# M_2_SoM_breakout_board_V1_0.net
KiCad netlist of a schematic drawn in EAGLE
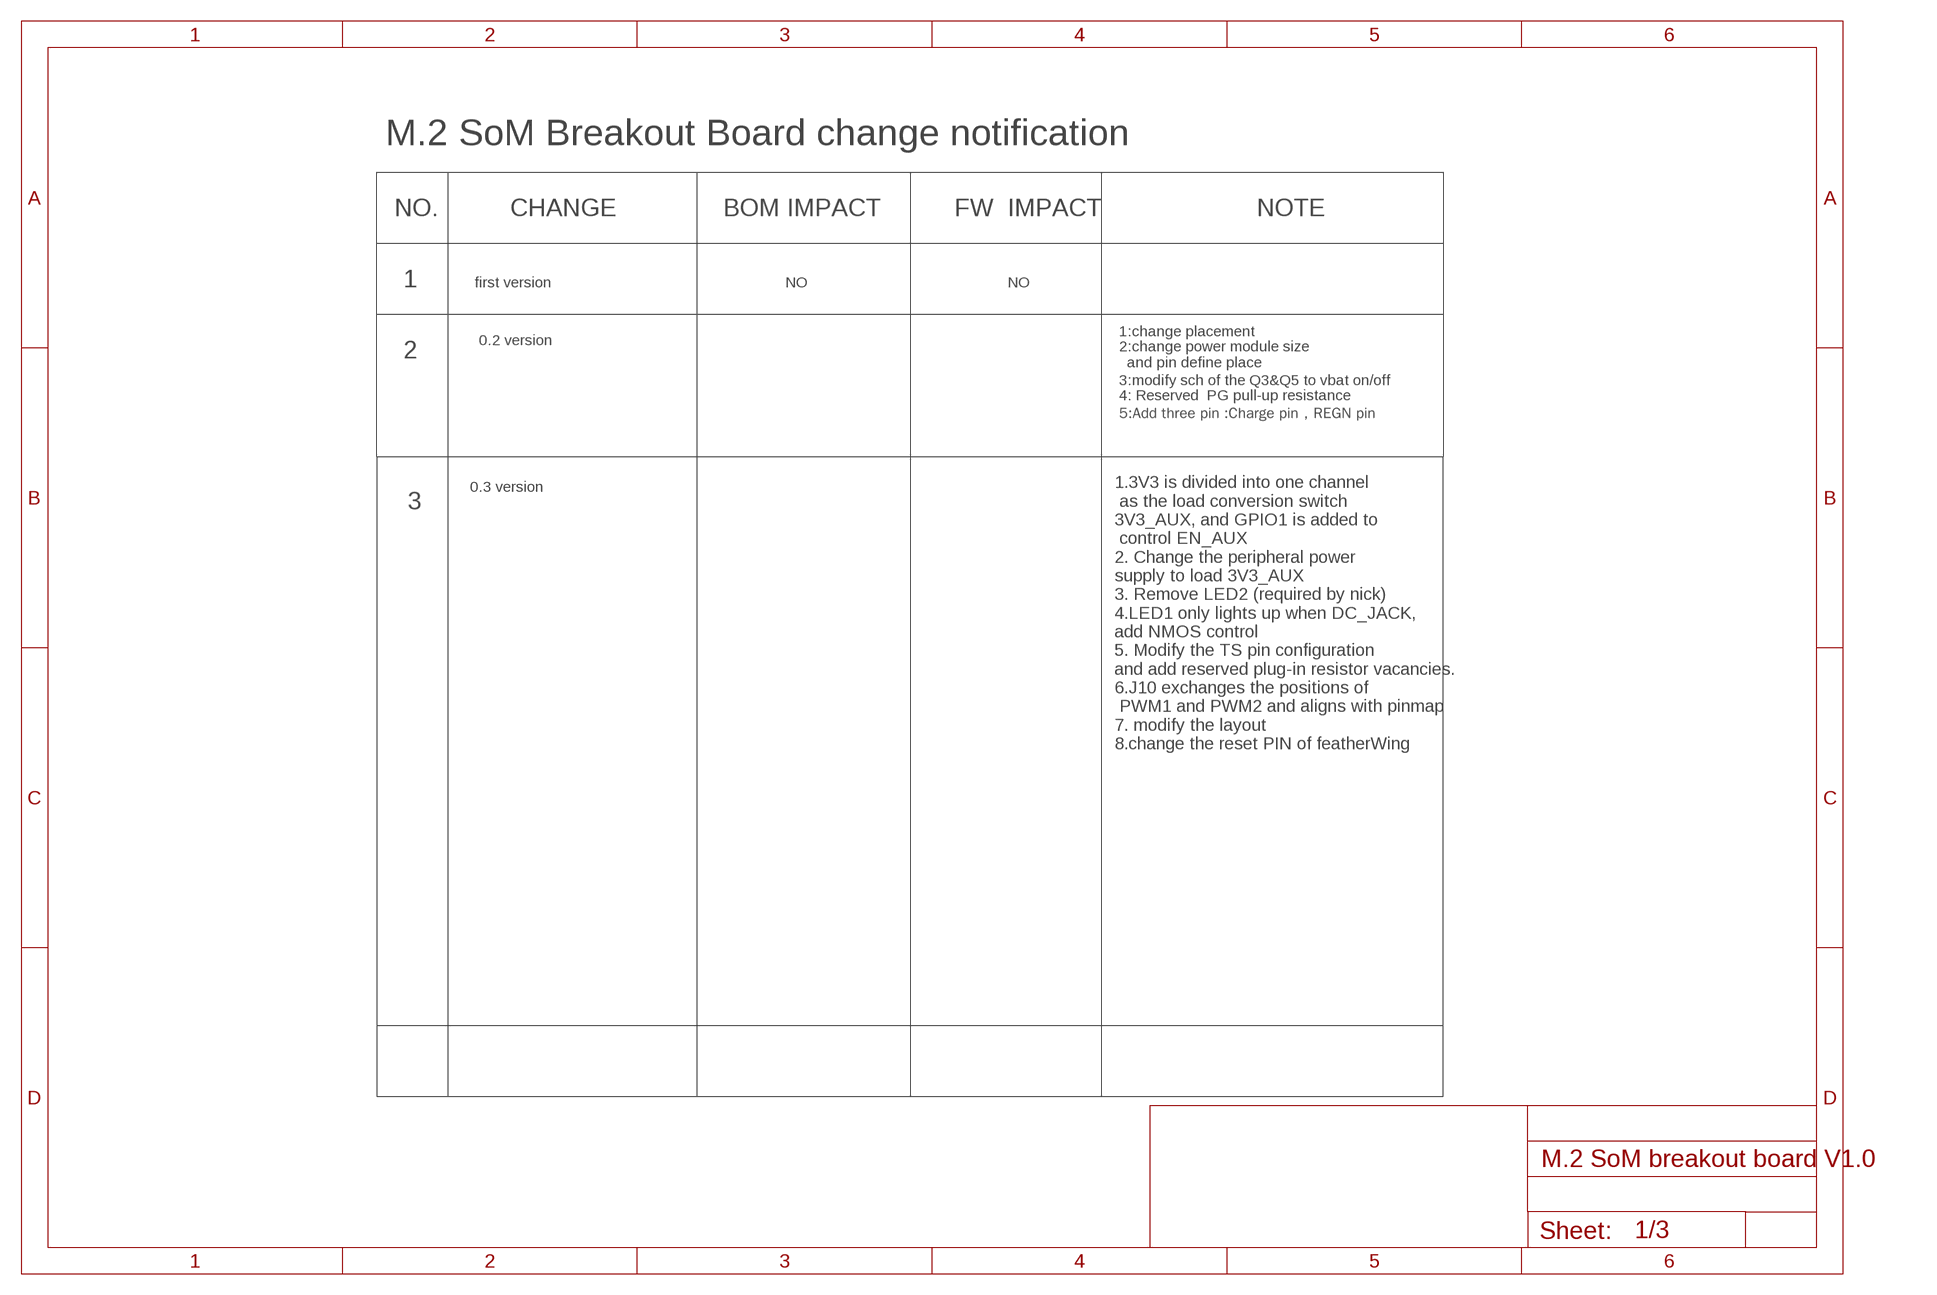
[diagram p0: schematic, sheet 1]
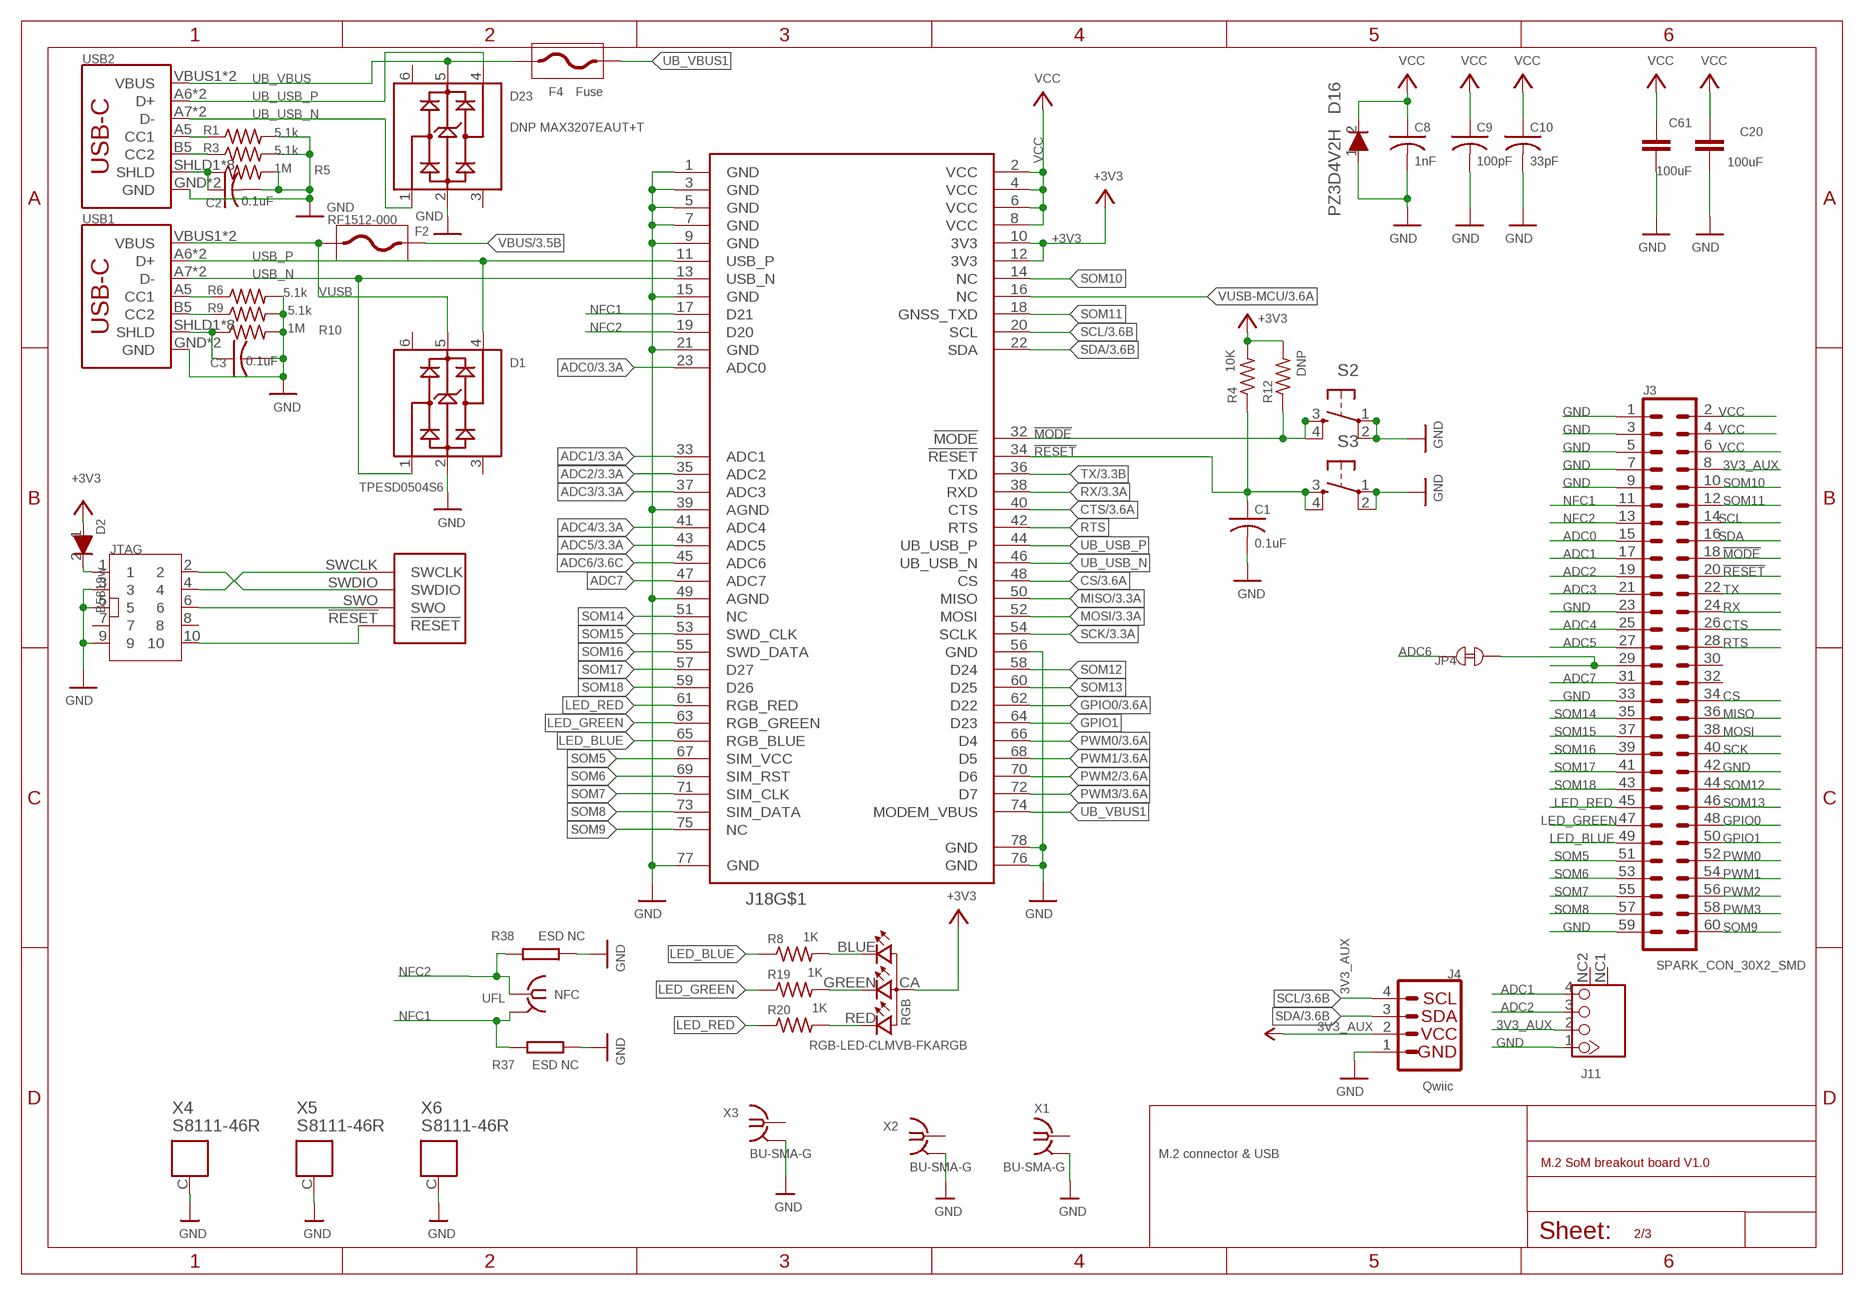
[diagram p1: schematic, sheet 2]
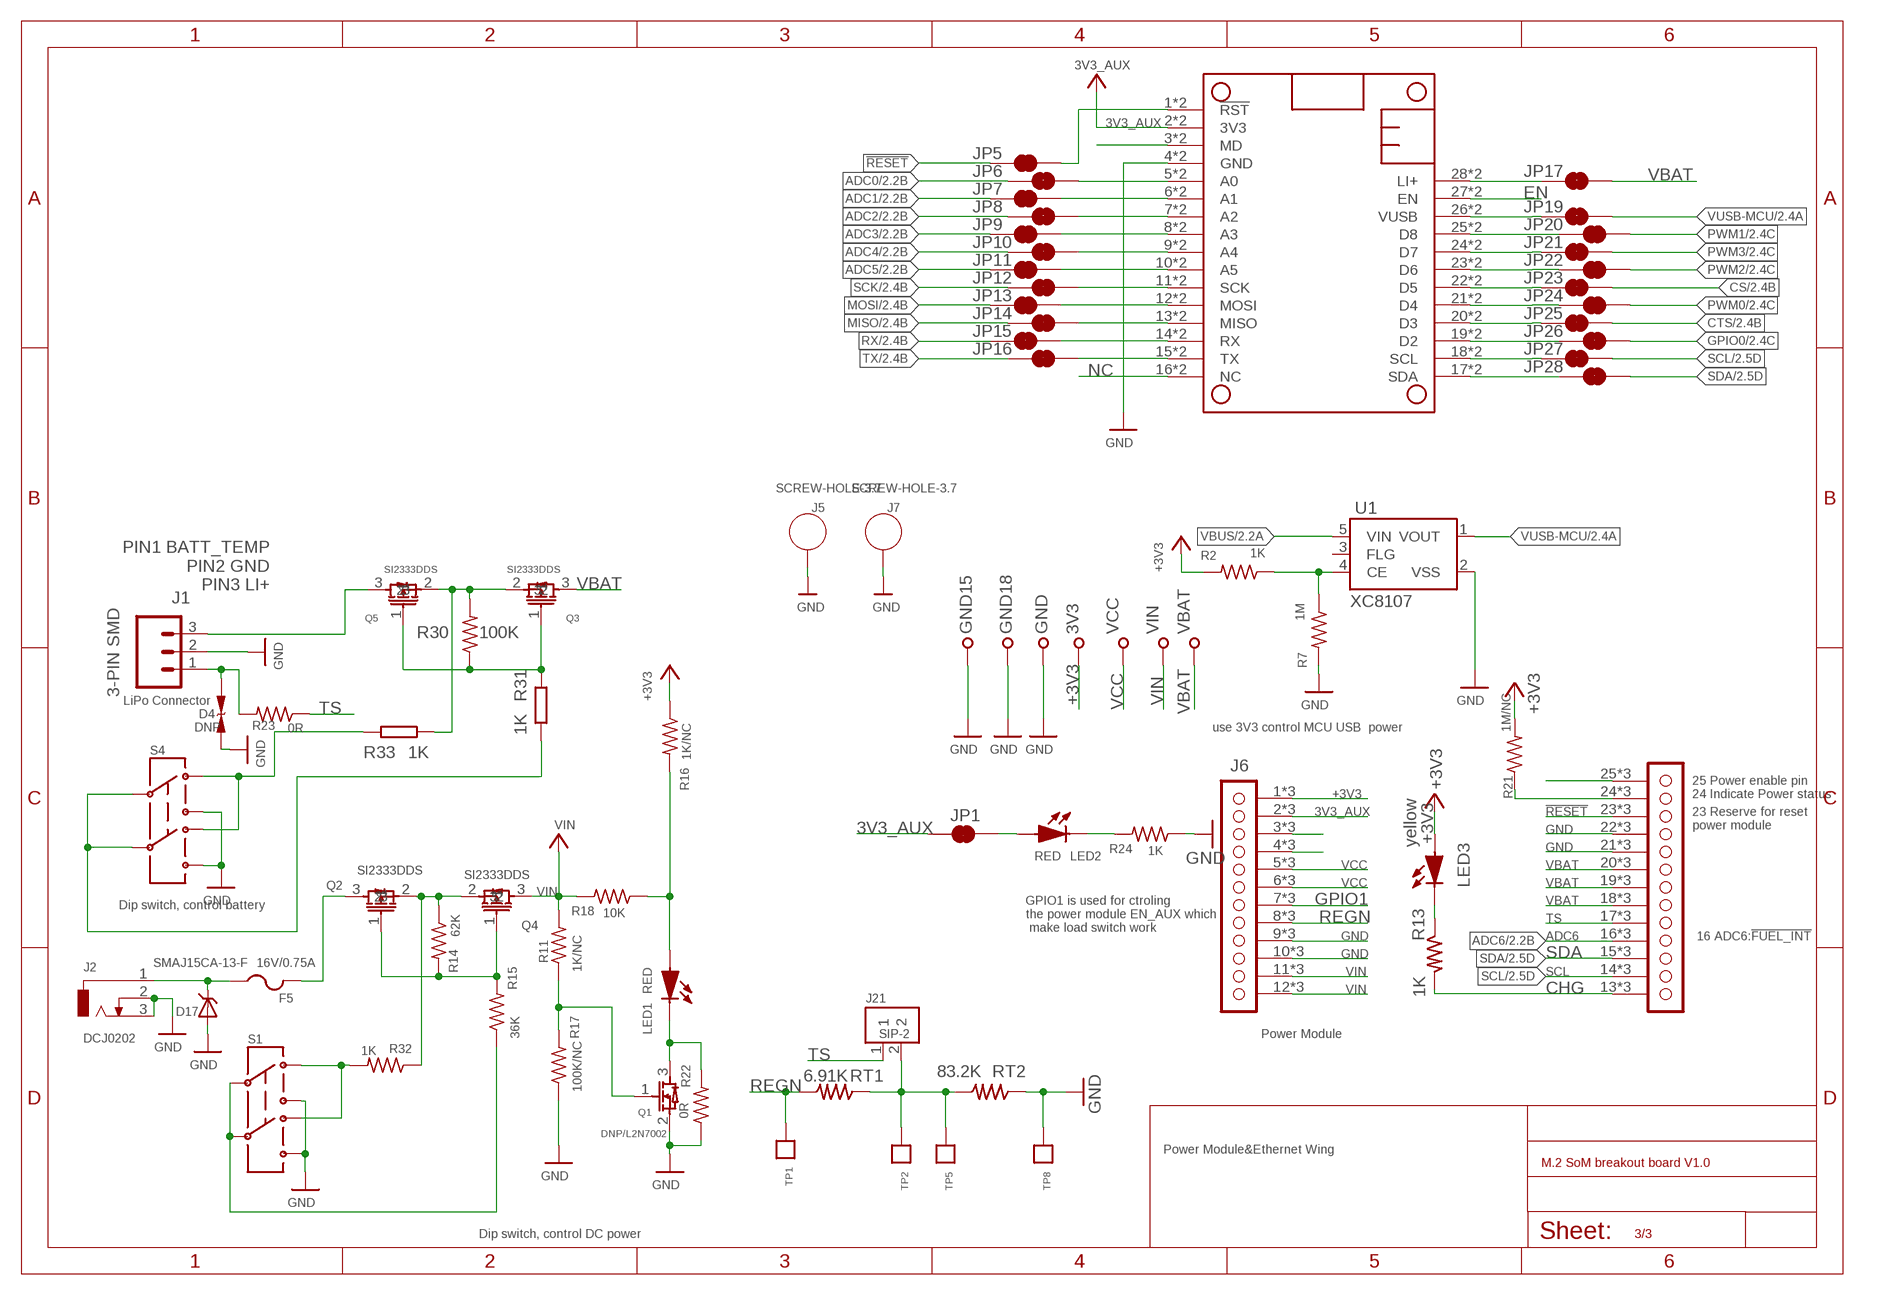
[diagram p2: schematic, sheet 3]

(export (version "E")
  (design (tool "Eeschema 10.0.6"))
  (components
    (comp (ref "C1")
      (value "0.1uF")
      (footprint "eagle-import:C0402_B")
      (libsource (lib "eagle-import") (part "C-US"))
    )
    (comp (ref "C2")
      (value "0.1uF")
      (footprint "eagle-import:C0402_B")
      (libsource (lib "eagle-import") (part "C-US"))
    )
    (comp (ref "C3")
      (value "0.1uF")
      (footprint "eagle-import:C0402_B")
      (libsource (lib "eagle-import") (part "C-US"))
    )
    (comp (ref "C8")
      (value "1nF")
      (footprint "eagle-import:C0402_B")
      (libsource (lib "eagle-import") (part "C-US"))
    )
    (comp (ref "C9")
      (value "100pF")
      (footprint "eagle-import:C0402_B")
      (libsource (lib "eagle-import") (part "C-US"))
    )
    (comp (ref "C10")
      (value "33pF")
      (footprint "eagle-import:C0402_B")
      (libsource (lib "eagle-import") (part "C-US"))
    )
    (comp (ref "C20")
      (value "100uF")
      (footprint "eagle-import:C1206K")
      (libsource (lib "eagle-import") (part "C-EUC1206K"))
    )
    (comp (ref "C61")
      (value "100uF")
      (footprint "eagle-import:C1206K")
      (libsource (lib "eagle-import") (part "C-EUC1206K"))
    )
    (comp (ref "D1")
      (value "TPESD0504S6")
      (footprint "eagle-import:SOT23-6")
      (fields (field (name "MFG") "MAXIM") (field (name "MPN") "MAX3207EAUT+T"))
      (libsource (lib "eagle-import") (part "MAX3207EAUT+T"))
    )
    (comp (ref "D2")
      (value "B5819w")
      (footprint "eagle-import:SOD-123")
      (libsource (lib "eagle-import") (part "DIODESOD123"))
    )
    (comp (ref "D16")
      (value "PZ3D4V2H")
      (footprint "eagle-import:SOD-323")
      (libsource (lib "eagle-import") (part "DIODESOD323"))
    )
    (comp (ref "D23")
      (value "DNP MAX3207EAUT+T")
      (footprint "eagle-import:SOT23-6")
      (fields (field (name "MFG") "MAXIM") (field (name "MPN") "MAX3207EAUT+T"))
      (libsource (lib "eagle-import") (part "MAX3207EAUT+T"))
    )
    (comp (ref "F2")
      (value "RF1512-000")
      (footprint "eagle-import:F0805")
      (libsource (lib "eagle-import") (part "FUSE"))
    )
    (comp (ref "F4")
      (value "Fuse")
      (footprint "eagle-import:F0805")
      (libsource (lib "eagle-import") (part "FUSE"))
    )
    (comp (ref "J3")
      (value "SPARK_CON_30X2_SMD")
      (footprint "eagle-import:SPARK_CON_30X2_SMD")
      (libsource (lib "eagle-import") (part "SPARK_CON_30X2_SMD"))
    )
    (comp (ref "J4")
      (value "QWIIC_CONNECTORJS-1MM")
      (footprint "eagle-import:1X04_1MM_RA")
      (libsource (lib "eagle-import") (part "QWIIC_CONNECTORJS-1MM"))
    )
    (comp (ref "J11")
      (value "WAFER-HY2.0-4PWB")
      (footprint "eagle-import:M.2-SOM-BREAKOUT-BOARD-V0.2-0228_WAFER-HY2.0-4PWB")
      (libsource (lib "eagle-import") (part "M.2-SOM-BREAKOUT-BOARD-V0.2-0228_WAFER-HY2.0-4PWB"))
    )
    (comp (ref "J18")
      (value "PARTICLE-STUDIOS_M_SERIES_M.2KEY")
      (footprint "eagle-import:PARTICLE-STUDIOS_PARTICLE_M.2EKEY_3.65MM_DRILL")
      (libsource (lib "eagle-import") (part "PARTICLE-STUDIOS_M_SERIES_M.2KEY"))
    )
    (comp (ref "JP4")
      (value "TP_SHORT")
      (footprint "eagle-import:TP_SHORT")
      (libsource (lib "eagle-import") (part "TP_SHORT"))
    )
    (comp (ref "JTAG")
      (value "CONN5X2")
      (footprint "eagle-import:CONN5X2_1.27")
      (fields (field (name "MFG") "KAWEEI") (field (name "MPN") "P6014A-M2GC-030-10"))
      (libsource (lib "eagle-import") (part "CONN5X2"))
    )
    (comp (ref "NFC")
      (value "UFL")
      (footprint "eagle-import:IPEX-20279-001E")
      (libsource (lib "eagle-import") (part "IPEX-20279-001E"))
    )
    (comp (ref "R1")
      (value "5.1k")
      (footprint "eagle-import:R0402_B")
      (libsource (lib "eagle-import") (part "R-US_"))
    )
    (comp (ref "R3")
      (value "5.1k")
      (footprint "eagle-import:R0402_B")
      (libsource (lib "eagle-import") (part "R-US_"))
    )
    (comp (ref "R4")
      (value "10K")
      (footprint "eagle-import:R0402_B")
      (libsource (lib "eagle-import") (part "R-US_"))
    )
    (comp (ref "R5")
      (value "1M")
      (footprint "eagle-import:R0402_B")
      (libsource (lib "eagle-import") (part "R-US_"))
    )
    (comp (ref "R6")
      (value "5.1k")
      (footprint "eagle-import:R0402_B")
      (libsource (lib "eagle-import") (part "R-US_"))
    )
    (comp (ref "R8")
      (value "1K")
      (footprint "eagle-import:R0402_B")
      (libsource (lib "eagle-import") (part "R-US_"))
    )
    (comp (ref "R9")
      (value "5.1k")
      (footprint "eagle-import:R0402_B")
      (libsource (lib "eagle-import") (part "R-US_"))
    )
    (comp (ref "R10")
      (value "1M")
      (footprint "eagle-import:R0402_B")
      (libsource (lib "eagle-import") (part "R-US_"))
    )
    (comp (ref "R12")
      (value "DNP")
      (footprint "eagle-import:R0402_B")
      (libsource (lib "eagle-import") (part "R-US_"))
    )
    (comp (ref "R19")
      (value "1K")
      (footprint "eagle-import:R0402_B")
      (libsource (lib "eagle-import") (part "R-US_"))
    )
    (comp (ref "R20")
      (value "1K")
      (footprint "eagle-import:R0402_B")
      (libsource (lib "eagle-import") (part "R-US_"))
    )
    (comp (ref "R37")
      (value "ESD NC")
      (footprint "eagle-import:R-0402S")
      (libsource (lib "eagle-import") (part "RES0402S"))
    )
    (comp (ref "R38")
      (value "ESD NC")
      (footprint "eagle-import:R-0402S")
      (libsource (lib "eagle-import") (part "RES0402S"))
    )
    (comp (ref "RGB")
      (value "RGB-LED-CLMVB-FKARGB")
      (footprint "eagle-import:PLCC4-2MM-RGB")
      (libsource (lib "eagle-import") (part "RGB-LED-CLMVB-FKARGB"))
    )
    (comp (ref "S2")
      (value "TAC_SWITCH")
      (footprint "eagle-import:TACTILE_SWITCH_4.2_3.2")
      (libsource (lib "eagle-import") (part "TAC_SWITCH"))
    )
    (comp (ref "S3")
      (value "TAC_SWITCH")
      (footprint "eagle-import:TACTILE_SWITCH_4.2_3.2")
      (libsource (lib "eagle-import") (part "TAC_SWITCH"))
    )
    (comp (ref "USB1")
      (value "USB_C16PIN")
      (footprint "eagle-import:USB-C-16P")
      (libsource (lib "eagle-import") (part "USB_C16PIN"))
    )
    (comp (ref "USB2")
      (value "USB_C16PIN")
      (footprint "eagle-import:USB-C-16P")
      (libsource (lib "eagle-import") (part "USB_C16PIN"))
    )
    (comp (ref "X1")
      (value "BU-SMA-G")
      (footprint "eagle-import:BU-SMA-G")
      (libsource (lib "eagle-import") (part "BU-SMA-G"))
    )
    (comp (ref "X2")
      (value "BU-SMA-G")
      (footprint "eagle-import:BU-SMA-G")
      (libsource (lib "eagle-import") (part "BU-SMA-G"))
    )
    (comp (ref "X3")
      (value "BU-SMA-G")
      (footprint "eagle-import:BU-SMA-G")
      (libsource (lib "eagle-import") (part "BU-SMA-G"))
    )
    (comp (ref "X4")
      (value "S8111-46R")
      (footprint "eagle-import:S8111-46R")
      (libsource (lib "eagle-import") (part "S8111-46R"))
    )
    (comp (ref "X5")
      (value "S8111-46R")
      (footprint "eagle-import:S8111-46R")
      (libsource (lib "eagle-import") (part "S8111-46R"))
    )
    (comp (ref "X6")
      (value "S8111-46R")
      (footprint "eagle-import:S8111-46R")
      (libsource (lib "eagle-import") (part "S8111-46R"))
    )
    (comp (ref "3V3")
      (value "TP-S2751-46R")
      (footprint "eagle-import:S2751-46R")
      (libsource (lib "eagle-import") (part "TP-S2751-46R"))
    )
    (comp (ref "D4")
      (value "DNP")
      (footprint "eagle-import:C0402")
      (libsource (lib "eagle-import") (part "ESD"))
    )
    (comp (ref "D17")
      (value "SMAJ15CA-13-F")
      (footprint "eagle-import:SMADIODE")
      (libsource (lib "eagle-import") (part "DIODE-ZENER"))
    )
    (comp (ref "F5")
      (value "16V/0.75A")
      (footprint "eagle-import:1812")
      (libsource (lib "eagle-import") (part "PTCFUSE-1812"))
    )
    (comp (ref "GND")
      (value "TP-S2751-46R")
      (footprint "eagle-import:S2751-46R")
      (libsource (lib "eagle-import") (part "TP-S2751-46R"))
    )
    (comp (ref "GND15")
      (value "TP-S2751-46R")
      (footprint "eagle-import:S2751-46R")
      (libsource (lib "eagle-import") (part "TP-S2751-46R"))
    )
    (comp (ref "GND18")
      (value "TP-S2751-46R")
      (footprint "eagle-import:S2751-46R")
      (libsource (lib "eagle-import") (part "TP-S2751-46R"))
    )
    (comp (ref "J1")
      (value "3-PIN SMD")
      (footprint "eagle-import:JST-3-SMD")
      (libsource (lib "eagle-import") (part "CONN_03JST-SMD"))
    )
    (comp (ref "J2")
      (value "DCJ0202")
      (footprint "eagle-import:DCJ0202")
      (libsource (lib "eagle-import") (part "DCJ0202"))
    )
    (comp (ref "J5")
      (value "SCREW-HOLE-3.7")
      (footprint "eagle-import:SCREW-HOLE-3.7")
      (libsource (lib "eagle-import") (part "SCREW-HOLE-3.7"))
    )
    (comp (ref "J6")
      (value "M.2-SOM-BREAKOUT-BOARD-V0.3_M.2-SOM-BREAKOUT-BOARD-V0.2-0228_PARTICLE-SZ_PARTICLE-POWER-MODULE")
      (footprint "eagle-import:M.2-SOM-BREAKOUT-BOARD-V0.3_M.2-SOM-BREAKOUT-BOARD-V0.2-0228_PARTICLE-SZ_PARTICLE-POWER-MODULE")
      (libsource (lib "eagle-import") (part "M.2-SOM-BREAKOUT-BOARD-V0.3_M.2-SOM-BREAKOUT-BOARD-V0.2-0228_PARTICLE-SZ_PARTICLE-POWER-MODULE"))
    )
    (comp (ref "J7")
      (value "SCREW-HOLE-3.7")
      (footprint "eagle-import:SCREW-HOLE-3.7")
      (libsource (lib "eagle-import") (part "SCREW-HOLE-3.7"))
    )
    (comp (ref "J21")
      (value "SIP-2")
      (footprint "eagle-import:SIP-2")
      (libsource (lib "eagle-import") (part "SIP-2"))
    )
    (comp (ref "JP1")
      (value "JUMPER-SMT_2_NC_TRACE_NO-SILK")
      (footprint "eagle-import:SMT-JUMPER_2_NC_TRACE_NO-SILK")
      (libsource (lib "eagle-import") (part "JUMPER-SMT_2_NC_TRACE_NO-SILK"))
    )
    (comp (ref "JP5")
      (value "JUMPER-SMT_2_NC_TRACE_NO-SILK")
      (footprint "eagle-import:SMT-JUMPER_2_NC_TRACE_NO-SILK")
      (libsource (lib "eagle-import") (part "JUMPER-SMT_2_NC_TRACE_NO-SILK"))
    )
    (comp (ref "JP6")
      (value "JUMPER-SMT_2_NC_TRACE_NO-SILK")
      (footprint "eagle-import:SMT-JUMPER_2_NC_TRACE_NO-SILK")
      (libsource (lib "eagle-import") (part "JUMPER-SMT_2_NC_TRACE_NO-SILK"))
    )
    (comp (ref "JP7")
      (value "JUMPER-SMT_2_NC_TRACE_NO-SILK")
      (footprint "eagle-import:SMT-JUMPER_2_NC_TRACE_NO-SILK")
      (libsource (lib "eagle-import") (part "JUMPER-SMT_2_NC_TRACE_NO-SILK"))
    )
    (comp (ref "JP8")
      (value "JUMPER-SMT_2_NC_TRACE_NO-SILK")
      (footprint "eagle-import:SMT-JUMPER_2_NC_TRACE_NO-SILK")
      (libsource (lib "eagle-import") (part "JUMPER-SMT_2_NC_TRACE_NO-SILK"))
    )
    (comp (ref "JP9")
      (value "JUMPER-SMT_2_NC_TRACE_NO-SILK")
      (footprint "eagle-import:SMT-JUMPER_2_NC_TRACE_NO-SILK")
      (libsource (lib "eagle-import") (part "JUMPER-SMT_2_NC_TRACE_NO-SILK"))
    )
    (comp (ref "JP10")
      (value "JUMPER-SMT_2_NC_TRACE_NO-SILK")
      (footprint "eagle-import:SMT-JUMPER_2_NC_TRACE_NO-SILK")
      (libsource (lib "eagle-import") (part "JUMPER-SMT_2_NC_TRACE_NO-SILK"))
    )
    (comp (ref "JP11")
      (value "JUMPER-SMT_2_NC_TRACE_NO-SILK")
      (footprint "eagle-import:SMT-JUMPER_2_NC_TRACE_NO-SILK")
      (libsource (lib "eagle-import") (part "JUMPER-SMT_2_NC_TRACE_NO-SILK"))
    )
    (comp (ref "JP12")
      (value "JUMPER-SMT_2_NC_TRACE_NO-SILK")
      (footprint "eagle-import:SMT-JUMPER_2_NC_TRACE_NO-SILK")
      (libsource (lib "eagle-import") (part "JUMPER-SMT_2_NC_TRACE_NO-SILK"))
    )
    (comp (ref "JP13")
      (value "JUMPER-SMT_2_NC_TRACE_NO-SILK")
      (footprint "eagle-import:SMT-JUMPER_2_NC_TRACE_NO-SILK")
      (libsource (lib "eagle-import") (part "JUMPER-SMT_2_NC_TRACE_NO-SILK"))
    )
    (comp (ref "JP14")
      (value "JUMPER-SMT_2_NC_TRACE_NO-SILK")
      (footprint "eagle-import:SMT-JUMPER_2_NC_TRACE_NO-SILK")
      (libsource (lib "eagle-import") (part "JUMPER-SMT_2_NC_TRACE_NO-SILK"))
    )
    (comp (ref "JP15")
      (value "JUMPER-SMT_2_NC_TRACE_NO-SILK")
      (footprint "eagle-import:SMT-JUMPER_2_NC_TRACE_NO-SILK")
      (libsource (lib "eagle-import") (part "JUMPER-SMT_2_NC_TRACE_NO-SILK"))
    )
    (comp (ref "JP16")
      (value "JUMPER-SMT_2_NC_TRACE_NO-SILK")
      (footprint "eagle-import:SMT-JUMPER_2_NC_TRACE_NO-SILK")
      (libsource (lib "eagle-import") (part "JUMPER-SMT_2_NC_TRACE_NO-SILK"))
    )
    (comp (ref "JP17")
      (value "JUMPER-SMT_2_NC_TRACE_NO-SILK")
      (footprint "eagle-import:SMT-JUMPER_2_NC_TRACE_NO-SILK")
      (libsource (lib "eagle-import") (part "JUMPER-SMT_2_NC_TRACE_NO-SILK"))
    )
    (comp (ref "JP19")
      (value "JUMPER-SMT_2_NC_TRACE_NO-SILK")
      (footprint "eagle-import:SMT-JUMPER_2_NC_TRACE_NO-SILK")
      (libsource (lib "eagle-import") (part "JUMPER-SMT_2_NC_TRACE_NO-SILK"))
    )
    (comp (ref "JP20")
      (value "JUMPER-SMT_2_NC_TRACE_NO-SILK")
      (footprint "eagle-import:SMT-JUMPER_2_NC_TRACE_NO-SILK")
      (libsource (lib "eagle-import") (part "JUMPER-SMT_2_NC_TRACE_NO-SILK"))
    )
    (comp (ref "JP21")
      (value "JUMPER-SMT_2_NC_TRACE_NO-SILK")
      (footprint "eagle-import:SMT-JUMPER_2_NC_TRACE_NO-SILK")
      (libsource (lib "eagle-import") (part "JUMPER-SMT_2_NC_TRACE_NO-SILK"))
    )
    (comp (ref "JP22")
      (value "JUMPER-SMT_2_NC_TRACE_NO-SILK")
      (footprint "eagle-import:SMT-JUMPER_2_NC_TRACE_NO-SILK")
      (libsource (lib "eagle-import") (part "JUMPER-SMT_2_NC_TRACE_NO-SILK"))
    )
    (comp (ref "JP23")
      (value "JUMPER-SMT_2_NC_TRACE_NO-SILK")
      (footprint "eagle-import:SMT-JUMPER_2_NC_TRACE_NO-SILK")
      (libsource (lib "eagle-import") (part "JUMPER-SMT_2_NC_TRACE_NO-SILK"))
    )
    (comp (ref "JP24")
      (value "JUMPER-SMT_2_NC_TRACE_NO-SILK")
      (footprint "eagle-import:SMT-JUMPER_2_NC_TRACE_NO-SILK")
      (libsource (lib "eagle-import") (part "JUMPER-SMT_2_NC_TRACE_NO-SILK"))
    )
    (comp (ref "JP25")
      (value "JUMPER-SMT_2_NC_TRACE_NO-SILK")
      (footprint "eagle-import:SMT-JUMPER_2_NC_TRACE_NO-SILK")
      (libsource (lib "eagle-import") (part "JUMPER-SMT_2_NC_TRACE_NO-SILK"))
    )
    (comp (ref "JP26")
      (value "JUMPER-SMT_2_NC_TRACE_NO-SILK")
      (footprint "eagle-import:SMT-JUMPER_2_NC_TRACE_NO-SILK")
      (libsource (lib "eagle-import") (part "JUMPER-SMT_2_NC_TRACE_NO-SILK"))
    )
    (comp (ref "JP27")
      (value "JUMPER-SMT_2_NC_TRACE_NO-SILK")
      (footprint "eagle-import:SMT-JUMPER_2_NC_TRACE_NO-SILK")
      (libsource (lib "eagle-import") (part "JUMPER-SMT_2_NC_TRACE_NO-SILK"))
    )
    (comp (ref "JP28")
      (value "JUMPER-SMT_2_NC_TRACE_NO-SILK")
      (footprint "eagle-import:SMT-JUMPER_2_NC_TRACE_NO-SILK")
      (libsource (lib "eagle-import") (part "JUMPER-SMT_2_NC_TRACE_NO-SILK"))
    )
    (comp (ref "LED1")
      (value "RED")
      (footprint "eagle-import:LED0603")
      (libsource (lib "eagle-import") (part "LED"))
    )
    (comp (ref "LED2")
      (value "RED")
      (footprint "eagle-import:LED0603")
      (libsource (lib "eagle-import") (part "LED"))
    )
    (comp (ref "LED3")
      (value "yellow")
      (footprint "eagle-import:LED0603")
      (libsource (lib "eagle-import") (part "LED"))
    )
    (comp (ref "MS1")
      (value "PARTICLE_MESH_SMTDUAL")
      (footprint "eagle-import:FEATHERWING_SMT2")
      (libsource (lib "eagle-import") (part "PARTICLE_MESH_SMTDUAL"))
    )
    (comp (ref "Q1")
      (value "DNP/L2N7002")
      (footprint "eagle-import:SOT323")
      (libsource (lib "eagle-import") (part "NMOSSOT323"))
    )
    (comp (ref "Q2")
      (value "SI2333DDS")
      (footprint "eagle-import:SOT-23")
      (libsource (lib "eagle-import") (part "PMOS"))
    )
    (comp (ref "Q3")
      (value "SI2333DDS")
      (footprint "eagle-import:SOT-23")
      (libsource (lib "eagle-import") (part "PMOS"))
    )
    (comp (ref "Q4")
      (value "SI2333DDS")
      (footprint "eagle-import:SOT-23")
      (libsource (lib "eagle-import") (part "PMOS"))
    )
    (comp (ref "Q5")
      (value "SI2333DDS")
      (footprint "eagle-import:SOT-23")
      (libsource (lib "eagle-import") (part "PMOS"))
    )
    (comp (ref "R2")
      (value "1K")
      (footprint "eagle-import:R0402_B")
      (libsource (lib "eagle-import") (part "R-US_"))
    )
    (comp (ref "R7")
      (value "1M")
      (footprint "eagle-import:R0402_B")
      (libsource (lib "eagle-import") (part "R-US_"))
    )
    (comp (ref "R11")
      (value "1K/NC")
      (footprint "eagle-import:R0402_B")
      (libsource (lib "eagle-import") (part "R-US_"))
    )
    (comp (ref "R13")
      (value "1K")
      (footprint "eagle-import:R-0402S")
      (libsource (lib "eagle-import") (part "particle SZ_RES0402S"))
    )
    (comp (ref "R14")
      (value "62K")
      (footprint "eagle-import:R0402_B")
      (libsource (lib "eagle-import") (part "R-US_"))
    )
    (comp (ref "R15")
      (value "36K")
      (footprint "eagle-import:R0402_B")
      (libsource (lib "eagle-import") (part "R-US_"))
    )
    (comp (ref "R16")
      (value "1K/NC")
      (footprint "eagle-import:R0402_B")
      (libsource (lib "eagle-import") (part "R-US_"))
    )
    (comp (ref "R17")
      (value "100K/NC")
      (footprint "eagle-import:R0402_B")
      (libsource (lib "eagle-import") (part "R-US_"))
    )
    (comp (ref "R18")
      (value "10K")
      (footprint "eagle-import:R0402_B")
      (libsource (lib "eagle-import") (part "R-US_"))
    )
    (comp (ref "R21")
      (value "1M/NC")
      (footprint "eagle-import:R0402_B")
      (libsource (lib "eagle-import") (part "R-US_"))
    )
    (comp (ref "R22")
      (value "0R")
      (footprint "eagle-import:R0402_B")
      (libsource (lib "eagle-import") (part "R-US_"))
    )
    (comp (ref "R23")
      (value "0R")
      (footprint "eagle-import:R0402_B")
      (libsource (lib "eagle-import") (part "R-US_"))
    )
    (comp (ref "R24")
      (value "1K")
      (footprint "eagle-import:R0402_B")
      (libsource (lib "eagle-import") (part "R-US_"))
    )
    (comp (ref "R30")
      (value "100K")
      (footprint "eagle-import:R0603_P")
      (libsource (lib "eagle-import") (part "RES_0603100K_"))
    )
    (comp (ref "R31")
      (value "1K")
      (footprint "eagle-import:R-0402S")
      (libsource (lib "eagle-import") (part "RES0402S"))
    )
    (comp (ref "R32")
      (value "1K")
      (footprint "eagle-import:R0402_B")
      (libsource (lib "eagle-import") (part "R-US_"))
    )
    (comp (ref "R33")
      (value "1K")
      (footprint "eagle-import:R-0402S")
      (libsource (lib "eagle-import") (part "RES0402S"))
    )
    (comp (ref "RT1")
      (value "6.91K")
      (footprint "eagle-import:R-0603A")
      (libsource (lib "eagle-import") (part "RESR0603A"))
    )
    (comp (ref "RT2")
      (value "83.2K")
      (footprint "eagle-import:R-0603A")
      (libsource (lib "eagle-import") (part "RESR0603A"))
    )
    (comp (ref "S1")
      (value "SWITCH-DPDT")
      (footprint "eagle-import:SWITCH-2.5X3.2-6")
      (libsource (lib "eagle-import") (part "SWITCH-DPDT"))
    )
    (comp (ref "S4")
      (value "SWITCH-DPDT")
      (footprint "eagle-import:SWITCH-2.5X3.2-6")
      (libsource (lib "eagle-import") (part "SWITCH-DPDT"))
    )
    (comp (ref "TP1")
      (value "TPTPEB")
      (footprint "eagle-import:TPEB")
      (libsource (lib "eagle-import") (part "TPTPEB"))
    )
    (comp (ref "TP2")
      (value "TPTPEB")
      (footprint "eagle-import:TPEB")
      (libsource (lib "eagle-import") (part "TPTPEB"))
    )
    (comp (ref "TP5")
      (value "TPTPEB")
      (footprint "eagle-import:TPEB")
      (libsource (lib "eagle-import") (part "TPTPEB"))
    )
    (comp (ref "TP8")
      (value "TPTPEB")
      (footprint "eagle-import:TPEB")
      (libsource (lib "eagle-import") (part "TPTPEB"))
    )
    (comp (ref "U1")
      (value "XC8107")
      (footprint "eagle-import:SOT25")
      (libsource (lib "eagle-import") (part "XC8107SOT25"))
    )
    (comp (ref "VBAT")
      (value "TP-S2751-46R")
      (footprint "eagle-import:S2751-46R")
      (libsource (lib "eagle-import") (part "TP-S2751-46R"))
    )
    (comp (ref "VCC")
      (value "TP-S2751-46R")
      (footprint "eagle-import:S2751-46R")
      (libsource (lib "eagle-import") (part "TP-S2751-46R"))
    )
    (comp (ref "VIN")
      (value "TP-S2751-46R")
      (footprint "eagle-import:S2751-46R")
      (libsource (lib "eagle-import") (part "TP-S2751-46R"))
    )
  )
  (nets
    (net (code "1") (name "+3V3") (class "Default")
      (node (ref "3V3") (pin "1") (pinfunction "TP_1") (pintype "bidirectional"))
      (node (ref "D2") (pin "1") (pinfunction "P$1_1") (pintype "bidirectional"))
      (node (ref "J18") (pin "10") (pinfunction "3V3_10") (pintype "power_in"))
      (node (ref "J18") (pin "12") (pinfunction "3V3_12") (pintype "power_in"))
      (node (ref "J6") (pin "1") (pinfunction "3V3_1") (pintype "passive"))
      (node (ref "J6") (pin "@1") (pinfunction "3V3_@1") (pintype "passive"))
      (node (ref "J6") (pin "P$1") (pinfunction "3V3_P$1") (pintype "passive"))
      (node (ref "LED3") (pin "1") (pinfunction "A_1") (pintype "bidirectional"))
      (node (ref "R12") (pin "2") (pinfunction "2_2") (pintype "passive"))
      (node (ref "R16") (pin "1") (pinfunction "1_1") (pintype "passive"))
      (node (ref "R2") (pin "2") (pinfunction "2_2") (pintype "passive"))
      (node (ref "R21") (pin "2") (pinfunction "2_2") (pintype "passive"))
      (node (ref "R4") (pin "2") (pinfunction "2_2") (pintype "passive"))
      (node (ref "RGB") (pin "CA") (pinfunction "1_CA") (pintype "passive"))
    )
    (net (code "2") (name "3V3_AUX") (class "Default")
      (node (ref "J11") (pin "2") (pinfunction "2_2") (pintype "bidirectional"))
      (node (ref "J3") (pin "8") (pinfunction "8_8") (pintype "passive"))
      (node (ref "J4") (pin "2") (pinfunction "2_2") (pintype "power_in"))
      (node (ref "J6") (pin "2") (pinfunction "3V3_2") (pintype "passive"))
      (node (ref "J6") (pin "@2") (pinfunction "3V3_@2") (pintype "passive"))
      (node (ref "J6") (pin "P$2") (pinfunction "3V3_P$2") (pintype "passive"))
      (node (ref "JP1") (pin "1") (pinfunction "1_1") (pintype "passive"))
      (node (ref "MS1") (pin "2") (pinfunction "3V3_2") (pintype "power_in"))
      (node (ref "MS1") (pin "2'") (pinfunction "3V3_2'") (pintype "power_in"))
    )
    (net (code "3") (name "ADC0") (class "Default")
      (node (ref "J18") (pin "23") (pinfunction "ADC0_23") (pintype "bidirectional"))
      (node (ref "J3") (pin "15") (pinfunction "15_15") (pintype "passive"))
      (node (ref "JP6") (pin "1") (pinfunction "1_1") (pintype "passive"))
    )
    (net (code "4") (name "ADC1") (class "Default")
      (node (ref "J11") (pin "4") (pinfunction "4_4") (pintype "bidirectional"))
      (node (ref "J18") (pin "33") (pinfunction "ADC1_33") (pintype "bidirectional"))
      (node (ref "J3") (pin "17") (pinfunction "17_17") (pintype "passive"))
      (node (ref "JP7") (pin "1") (pinfunction "1_1") (pintype "passive"))
    )
    (net (code "5") (name "ADC2") (class "Default")
      (node (ref "J11") (pin "3") (pinfunction "3_3") (pintype "bidirectional"))
      (node (ref "J18") (pin "35") (pinfunction "ADC2_35") (pintype "bidirectional"))
      (node (ref "J3") (pin "19") (pinfunction "19_19") (pintype "passive"))
      (node (ref "JP8") (pin "1") (pinfunction "1_1") (pintype "passive"))
    )
    (net (code "6") (name "ADC3") (class "Default")
      (node (ref "J18") (pin "37") (pinfunction "ADC3_37") (pintype "bidirectional"))
      (node (ref "J3") (pin "21") (pinfunction "21_21") (pintype "passive"))
      (node (ref "JP9") (pin "1") (pinfunction "1_1") (pintype "passive"))
    )
    (net (code "7") (name "ADC4") (class "Default")
      (node (ref "J18") (pin "41") (pinfunction "ADC4_41") (pintype "bidirectional"))
      (node (ref "J3") (pin "25") (pinfunction "25_25") (pintype "passive"))
      (node (ref "JP10") (pin "1") (pinfunction "1_1") (pintype "passive"))
    )
    (net (code "8") (name "ADC5") (class "Default")
      (node (ref "J18") (pin "43") (pinfunction "ADC5_43") (pintype "bidirectional"))
      (node (ref "J3") (pin "27") (pinfunction "27_27") (pintype "passive"))
      (node (ref "JP11") (pin "1") (pinfunction "1_1") (pintype "passive"))
    )
    (net (code "9") (name "ADC6") (class "Default")
      (node (ref "J18") (pin "45") (pinfunction "ADC6_45") (pintype "bidirectional"))
      (node (ref "J6") (pin "16") (pinfunction "~{FUEL-INT}_16") (pintype "passive"))
      (node (ref "J6") (pin "@16") (pinfunction "~{FUEL-INT}_@16") (pintype "passive"))
      (node (ref "J6") (pin "P$16") (pinfunction "~{FUEL-INT}_P$16") (pintype "passive"))
      (node (ref "JP4") (pin "2") (pinfunction "2_2") (pintype "bidirectional"))
    )
    (net (code "10") (name "ADC7") (class "Default")
      (node (ref "J18") (pin "47") (pinfunction "ADC7_47") (pintype "bidirectional"))
      (node (ref "J3") (pin "31") (pinfunction "31_31") (pintype "passive"))
    )
    (net (code "11") (name "CHG") (class "Default")
      (node (ref "J6") (pin "13") (pinfunction "CHG_13") (pintype "passive"))
      (node (ref "J6") (pin "@13") (pinfunction "CHG_@13") (pintype "passive"))
      (node (ref "J6") (pin "P$13") (pinfunction "CHG_P$13") (pintype "passive"))
      (node (ref "R13") (pin "2") (pinfunction "2_2") (pintype "bidirectional"))
    )
    (net (code "12") (name "CS") (class "Default")
      (node (ref "J18") (pin "48") (pinfunction "CS_48") (pintype "bidirectional"))
      (node (ref "J3") (pin "34") (pinfunction "34_34") (pintype "passive"))
      (node (ref "JP23") (pin "2") (pinfunction "2_2") (pintype "passive"))
    )
    (net (code "13") (name "CTS") (class "Default")
      (node (ref "J18") (pin "40") (pinfunction "CTS_40") (pintype "bidirectional"))
      (node (ref "J3") (pin "26") (pinfunction "26_26") (pintype "passive"))
      (node (ref "JP25") (pin "2") (pinfunction "2_2") (pintype "passive"))
    )
    (net (code "14") (name "EN") (class "Default")
      (node (ref "MS1") (pin "27") (pinfunction "EN_27") (pintype "passive"))
      (node (ref "MS1") (pin "27'") (pinfunction "EN_27'") (pintype "passive"))
    )
    (net (code "15") (name "GND") (class "Default")
      (node (ref "C1") (pin "2") (pinfunction "2_2") (pintype "passive"))
      (node (ref "C10") (pin "2") (pinfunction "2_2") (pintype "passive"))
      (node (ref "C2") (pin "2") (pinfunction "2_2") (pintype "passive"))
      (node (ref "C20") (pin "2") (pinfunction "2_2") (pintype "passive"))
      (node (ref "C3") (pin "2") (pinfunction "2_2") (pintype "passive"))
      (node (ref "C61") (pin "2") (pinfunction "2_2") (pintype "passive"))
      (node (ref "C8") (pin "2") (pinfunction "2_2") (pintype "passive"))
      (node (ref "C9") (pin "2") (pinfunction "2_2") (pintype "passive"))
      (node (ref "D1") (pin "2") (pinfunction "2_2") (pintype "bidirectional"))
      (node (ref "D16") (pin "1") (pinfunction "P$1_1") (pintype "bidirectional"))
      (node (ref "D17") (pin "A") (pinfunction "A_A") (pintype "passive"))
      (node (ref "D23") (pin "2") (pinfunction "2_2") (pintype "bidirectional"))
      (node (ref "D4") (pin "1") (pinfunction "1_1") (pintype "bidirectional"))
      (node (ref "GND") (pin "1") (pinfunction "TP_1") (pintype "bidirectional"))
      (node (ref "GND15") (pin "1") (pinfunction "TP_1") (pintype "bidirectional"))
      (node (ref "GND18") (pin "1") (pinfunction "TP_1") (pintype "bidirectional"))
      (node (ref "J1") (pin "2") (pinfunction "2_2") (pintype "passive"))
      (node (ref "J11") (pin "1") (pinfunction "1_1") (pintype "bidirectional"))
      (node (ref "J18") (pin "1") (pinfunction "GND_1") (pintype "power_in"))
      (node (ref "J18") (pin "15") (pinfunction "GND_15") (pintype "power_in"))
      (node (ref "J18") (pin "21") (pinfunction "GND_21") (pintype "power_in"))
      (node (ref "J18") (pin "3") (pinfunction "GND_3") (pintype "power_in"))
      (node (ref "J18") (pin "39") (pinfunction "AGND_39") (pintype "power_in"))
      (node (ref "J18") (pin "49") (pinfunction "AGND_49") (pintype "power_in"))
      (node (ref "J18") (pin "5") (pinfunction "GND_5") (pintype "power_in"))
      (node (ref "J18") (pin "56") (pinfunction "GND_56") (pintype "power_in"))
      (node (ref "J18") (pin "7") (pinfunction "GND_7") (pintype "power_in"))
      (node (ref "J18") (pin "76") (pinfunction "GND_76") (pintype "power_in"))
      (node (ref "J18") (pin "77") (pinfunction "GND_77") (pintype "power_in"))
      (node (ref "J18") (pin "78") (pinfunction "GND_78") (pintype "power_in"))
      (node (ref "J18") (pin "9") (pinfunction "GND_9") (pintype "power_in"))
      (node (ref "J2") (pin "2") (pinfunction "2_2") (pintype "passive"))
      (node (ref "J2") (pin "3") (pinfunction "3_3") (pintype "passive"))
      (node (ref "J3") (pin "1") (pinfunction "1_1") (pintype "passive"))
      (node (ref "J3") (pin "23") (pinfunction "23_23") (pintype "passive"))
      (node (ref "J3") (pin "3") (pinfunction "3_3") (pintype "passive"))
      (node (ref "J3") (pin "33") (pinfunction "33_33") (pintype "passive"))
      (node (ref "J3") (pin "42") (pinfunction "42_42") (pintype "passive"))
      (node (ref "J3") (pin "5") (pinfunction "5_5") (pintype "passive"))
      (node (ref "J3") (pin "59") (pinfunction "59_59") (pintype "passive"))
      (node (ref "J3") (pin "7") (pinfunction "7_7") (pintype "passive"))
      (node (ref "J3") (pin "9") (pinfunction "9_9") (pintype "passive"))
      (node (ref "J4") (pin "1") (pinfunction "1_1") (pintype "power_in"))
      (node (ref "J5") (pin "P$1") (pinfunction "GND_P$1") (pintype "bidirectional"))
      (node (ref "J6") (pin "10") (pinfunction "GND_10") (pintype "passive"))
      (node (ref "J6") (pin "21") (pinfunction "GND_21") (pintype "passive"))
      (node (ref "J6") (pin "22") (pinfunction "GND_22") (pintype "passive"))
      (node (ref "J6") (pin "9") (pinfunction "GND_9") (pintype "passive"))
      (node (ref "J6") (pin "@10") (pinfunction "GND_@10") (pintype "passive"))
      (node (ref "J6") (pin "@21") (pinfunction "GND_@21") (pintype "passive"))
      (node (ref "J6") (pin "@22") (pinfunction "GND_@22") (pintype "passive"))
      (node (ref "J6") (pin "@9") (pinfunction "GND_@9") (pintype "passive"))
      (node (ref "J6") (pin "P$10") (pinfunction "GND_P$10") (pintype "passive"))
      (node (ref "J6") (pin "P$21") (pinfunction "GND_P$21") (pintype "passive"))
      (node (ref "J6") (pin "P$22") (pinfunction "GND_P$22") (pintype "passive"))
      (node (ref "J6") (pin "P$9") (pinfunction "GND_P$9") (pintype "passive"))
      (node (ref "J7") (pin "P$1") (pinfunction "GND_P$1") (pintype "bidirectional"))
      (node (ref "JTAG") (pin "3") (pinfunction "3_3") (pintype "bidirectional"))
      (node (ref "JTAG") (pin "5") (pinfunction "5_5") (pintype "bidirectional"))
      (node (ref "JTAG") (pin "9") (pinfunction "9_9") (pintype "bidirectional"))
      (node (ref "MS1") (pin "4") (pinfunction "GND_4") (pintype "power_in"))
      (node (ref "MS1") (pin "4'") (pinfunction "GND_4'") (pintype "power_in"))
      (node (ref "Q1") (pin "2") (pinfunction "2_2") (pintype "bidirectional"))
      (node (ref "R1") (pin "2") (pinfunction "2_2") (pintype "passive"))
      (node (ref "R10") (pin "2") (pinfunction "2_2") (pintype "passive"))
      (node (ref "R17") (pin "1") (pinfunction "1_1") (pintype "passive"))
      (node (ref "R22") (pin "1") (pinfunction "1_1") (pintype "passive"))
      (node (ref "R24") (pin "1") (pinfunction "1_1") (pintype "passive"))
      (node (ref "R3") (pin "2") (pinfunction "2_2") (pintype "passive"))
      (node (ref "R37") (pin "2") (pinfunction "2_2") (pintype "bidirectional"))
      (node (ref "R38") (pin "1") (pinfunction "1_1") (pintype "bidirectional"))
      (node (ref "R5") (pin "2") (pinfunction "2_2") (pintype "passive"))
      (node (ref "R6") (pin "2") (pinfunction "2_2") (pintype "passive"))
      (node (ref "R7") (pin "2") (pinfunction "2_2") (pintype "passive"))
      (node (ref "R9") (pin "2") (pinfunction "2_2") (pintype "passive"))
      (node (ref "RT2") (pin "1") (pinfunction "1_1") (pintype "bidirectional"))
      (node (ref "S1") (pin "3") (pinfunction "3_3") (pintype "bidirectional"))
      (node (ref "S1") (pin "6") (pinfunction "6_6") (pintype "bidirectional"))
      (node (ref "S2") (pin "1") (pinfunction "1_1") (pintype "passive"))
      (node (ref "S2") (pin "2") (pinfunction "2_2") (pintype "passive"))
      (node (ref "S3") (pin "1") (pinfunction "1_1") (pintype "passive"))
      (node (ref "S3") (pin "2") (pinfunction "2_2") (pintype "passive"))
      (node (ref "S4") (pin "3") (pinfunction "3_3") (pintype "bidirectional"))
      (node (ref "S4") (pin "6") (pinfunction "6_6") (pintype "bidirectional"))
      (node (ref "TP8") (pin "1") (pinfunction "1_1") (pintype "bidirectional"))
      (node (ref "U1") (pin "2") (pinfunction "VSS_2") (pintype "power_in"))
      (node (ref "USB1") (pin "GND") (pinfunction "GND_GND") (pintype "bidirectional"))
      (node (ref "USB1") (pin "GND2") (pinfunction "GND_GND2") (pintype "bidirectional"))
      (node (ref "USB2") (pin "GND") (pinfunction "GND_GND") (pintype "bidirectional"))
      (node (ref "USB2") (pin "GND2") (pinfunction "GND_GND2") (pintype "bidirectional"))
      (node (ref "X1") (pin "2") (pinfunction "2_2") (pintype "passive"))
      (node (ref "X1") (pin "3") (pinfunction "2_3") (pintype "passive"))
      (node (ref "X1") (pin "4") (pinfunction "2_4") (pintype "passive"))
      (node (ref "X1") (pin "5") (pinfunction "2_5") (pintype "passive"))
      (node (ref "X2") (pin "2") (pinfunction "2_2") (pintype "passive"))
      (node (ref "X2") (pin "3") (pinfunction "2_3") (pintype "passive"))
      (node (ref "X2") (pin "4") (pinfunction "2_4") (pintype "passive"))
      (node (ref "X2") (pin "5") (pinfunction "2_5") (pintype "passive"))
      (node (ref "X3") (pin "2") (pinfunction "2_2") (pintype "passive"))
      (node (ref "X3") (pin "3") (pinfunction "2_3") (pintype "passive"))
      (node (ref "X3") (pin "4") (pinfunction "2_4") (pintype "passive"))
      (node (ref "X3") (pin "5") (pinfunction "2_5") (pintype "passive"))
      (node (ref "X4") (pin "C") (pinfunction "C_C") (pintype "power_in"))
      (node (ref "X5") (pin "C") (pinfunction "C_C") (pintype "power_in"))
      (node (ref "X6") (pin "C") (pinfunction "C_C") (pintype "power_in"))
    )
    (net (code "16") (name "GPIO0") (class "Default")
      (node (ref "J18") (pin "62") (pinfunction "D22_62") (pintype "bidirectional"))
      (node (ref "J3") (pin "48") (pinfunction "48_48") (pintype "passive"))
      (node (ref "JP26") (pin "2") (pinfunction "2_2") (pintype "passive"))
    )
    (net (code "17") (name "GPIO1") (class "Default")
      (node (ref "J18") (pin "64") (pinfunction "D23_64") (pintype "bidirectional"))
      (node (ref "J3") (pin "50") (pinfunction "50_50") (pintype "passive"))
      (node (ref "J6") (pin "7") (pinfunction "REGN_7") (pintype "passive"))
      (node (ref "J6") (pin "@7") (pinfunction "REGN_@7") (pintype "passive"))
      (node (ref "J6") (pin "P$7") (pinfunction "REGN_P$7") (pintype "passive"))
    )
    (net (code "18") (name "LED_BLUE") (class "Default")
      (node (ref "J18") (pin "65") (pinfunction "RGB_BLUE_65") (pintype "bidirectional"))
      (node (ref "J3") (pin "49") (pinfunction "49_49") (pintype "passive"))
      (node (ref "R8") (pin "1") (pinfunction "1_1") (pintype "passive"))
    )
    (net (code "19") (name "LED_GREEN") (class "Default")
      (node (ref "J18") (pin "63") (pinfunction "RGB_GREEN_63") (pintype "bidirectional"))
      (node (ref "J3") (pin "47") (pinfunction "47_47") (pintype "passive"))
      (node (ref "R19") (pin "1") (pinfunction "1_1") (pintype "passive"))
    )
    (net (code "20") (name "LED_RED") (class "Default")
      (node (ref "J18") (pin "61") (pinfunction "RGB_RED_61") (pintype "bidirectional"))
      (node (ref "J3") (pin "45") (pinfunction "45_45") (pintype "passive"))
      (node (ref "R20") (pin "1") (pinfunction "1_1") (pintype "passive"))
    )
    (net (code "21") (name "MISO") (class "Default")
      (node (ref "J18") (pin "50") (pinfunction "MISO_50") (pintype "bidirectional"))
      (node (ref "J3") (pin "36") (pinfunction "36_36") (pintype "passive"))
      (node (ref "JP14") (pin "1") (pinfunction "1_1") (pintype "passive"))
    )
    (net (code "22") (name "MOSI") (class "Default")
      (node (ref "J18") (pin "52") (pinfunction "MOSI_52") (pintype "bidirectional"))
      (node (ref "J3") (pin "38") (pinfunction "38_38") (pintype "passive"))
      (node (ref "JP13") (pin "1") (pinfunction "1_1") (pintype "passive"))
    )
    (net (code "23") (name "NC") (class "Default")
      (node (ref "MS1") (pin "16") (pinfunction "NC_16") (pintype "passive"))
      (node (ref "MS1") (pin "16'") (pinfunction "NC_16'") (pintype "passive"))
    )
    (net (code "24") (name "NFC1") (class "Default")
      (node (ref "J18") (pin "17") (pinfunction "D21_17") (pintype "bidirectional"))
      (node (ref "J3") (pin "11") (pinfunction "11_11") (pintype "passive"))
      (node (ref "NFC") (pin "2@1") (pinfunction "GND_2@1") (pintype "passive"))
      (node (ref "NFC") (pin "2@2") (pinfunction "GND_2@2") (pintype "passive"))
      (node (ref "R37") (pin "1") (pinfunction "1_1") (pintype "bidirectional"))
    )
    (net (code "25") (name "NFC2") (class "Default")
      (node (ref "J18") (pin "19") (pinfunction "D20_19") (pintype "bidirectional"))
      (node (ref "J3") (pin "13") (pinfunction "13_13") (pintype "passive"))
      (node (ref "NFC") (pin "1") (pinfunction "1_1") (pintype "passive"))
      (node (ref "R38") (pin "2") (pinfunction "2_2") (pintype "bidirectional"))
    )
    (net (code "26") (name "Net-(C2-Pad1)") (class "Default")
      (node (ref "C2") (pin "1") (pinfunction "1_1") (pintype "passive"))
      (node (ref "R5") (pin "1") (pinfunction "1_1") (pintype "passive"))
      (node (ref "USB2") (pin "SHLD1") (pinfunction "SHLD_SHLD1") (pintype "bidirectional"))
      (node (ref "USB2") (pin "SHLD2") (pinfunction "SHLD_SHLD2") (pintype "bidirectional"))
      (node (ref "USB2") (pin "SHLD3") (pinfunction "SHLD_SHLD3") (pintype "bidirectional"))
      (node (ref "USB2") (pin "SHLD4") (pinfunction "SHLD_SHLD4") (pintype "bidirectional"))
      (node (ref "USB2") (pin "SHLD5") (pinfunction "SHLD_SHLD5") (pintype "bidirectional"))
      (node (ref "USB2") (pin "SHLD6") (pinfunction "SHLD_SHLD6") (pintype "bidirectional"))
      (node (ref "USB2") (pin "SHLD7") (pinfunction "SHLD_SHLD7") (pintype "bidirectional"))
      (node (ref "USB2") (pin "SHLD8") (pinfunction "SHLD_SHLD8") (pintype "bidirectional"))
    )
    (net (code "27") (name "Net-(C3-Pad1)") (class "Default")
      (node (ref "C3") (pin "1") (pinfunction "1_1") (pintype "passive"))
      (node (ref "R10") (pin "1") (pinfunction "1_1") (pintype "passive"))
      (node (ref "USB1") (pin "SHLD1") (pinfunction "SHLD_SHLD1") (pintype "bidirectional"))
      (node (ref "USB1") (pin "SHLD2") (pinfunction "SHLD_SHLD2") (pintype "bidirectional"))
      (node (ref "USB1") (pin "SHLD3") (pinfunction "SHLD_SHLD3") (pintype "bidirectional"))
      (node (ref "USB1") (pin "SHLD4") (pinfunction "SHLD_SHLD4") (pintype "bidirectional"))
      (node (ref "USB1") (pin "SHLD5") (pinfunction "SHLD_SHLD5") (pintype "bidirectional"))
      (node (ref "USB1") (pin "SHLD6") (pinfunction "SHLD_SHLD6") (pintype "bidirectional"))
      (node (ref "USB1") (pin "SHLD7") (pinfunction "SHLD_SHLD7") (pintype "bidirectional"))
      (node (ref "USB1") (pin "SHLD8") (pinfunction "SHLD_SHLD8") (pintype "bidirectional"))
    )
    (net (code "28") (name "Net-(D2-P$2)") (class "Default")
      (node (ref "D2") (pin "2") (pinfunction "P$2_2") (pintype "bidirectional"))
      (node (ref "JTAG") (pin "1") (pinfunction "1_1") (pintype "bidirectional"))
    )
    (net (code "29") (name "Net-(D4-Pad2)") (class "Default")
      (node (ref "D4") (pin "2") (pinfunction "2_2") (pintype "bidirectional"))
      (node (ref "J1") (pin "1") (pinfunction "1_1") (pintype "passive"))
      (node (ref "R23") (pin "2") (pinfunction "2_2") (pintype "passive"))
    )
    (net (code "30") (name "Net-(D17-PadC)") (class "Default")
      (node (ref "D17") (pin "C") (pinfunction "C_C") (pintype "passive"))
      (node (ref "F5") (pin "1") (pinfunction "1_1") (pintype "passive"))
      (node (ref "J2") (pin "1") (pinfunction "1_1") (pintype "passive"))
    )
    (net (code "31") (name "Net-(F5-Pad2)") (class "Default")
      (node (ref "F5") (pin "2") (pinfunction "2_2") (pintype "passive"))
      (node (ref "Q2") (pin "3") (pinfunction "3_3") (pintype "bidirectional"))
    )
    (net (code "32") (name "Net-(J1-Pad3)") (class "Default")
      (node (ref "J1") (pin "3") (pinfunction "3_3") (pintype "passive"))
      (node (ref "Q5") (pin "3") (pinfunction "3_3") (pintype "bidirectional"))
    )
    (net (code "33") (name "Net-(J3-Pad29)") (class "Default")
      (node (ref "J3") (pin "29") (pinfunction "29_29") (pintype "passive"))
      (node (ref "JP4") (pin "1") (pinfunction "1_1") (pintype "bidirectional"))
    )
    (net (code "34") (name "Net-(J6-5DC-Pad3)") (class "Default")
      (node (ref "J6") (pin "3") (pinfunction "5DC_3") (pintype "passive"))
      (node (ref "J6") (pin "@3") (pinfunction "5DC_@3") (pintype "passive"))
      (node (ref "J6") (pin "P$3") (pinfunction "5DC_P$3") (pintype "passive"))
    )
    (net (code "35") (name "Net-(J6-5DC-Pad4)") (class "Default")
      (node (ref "J6") (pin "4") (pinfunction "5DC_4") (pintype "passive"))
      (node (ref "J6") (pin "@4") (pinfunction "5DC_@4") (pintype "passive"))
      (node (ref "J6") (pin "P$4") (pinfunction "5DC_P$4") (pintype "passive"))
    )
    (net (code "36") (name "Net-(J6-ENABLE-Pad25)") (class "Default")
      (node (ref "J6") (pin "25") (pinfunction "ENABLE_25") (pintype "passive"))
      (node (ref "J6") (pin "@25") (pinfunction "ENABLE_@25") (pintype "passive"))
      (node (ref "J6") (pin "P$25") (pinfunction "ENABLE_P$25") (pintype "passive"))
    )
    (net (code "37") (name "Net-(J6-PG-Pad24)") (class "Default")
      (node (ref "J6") (pin "24") (pinfunction "PG_24") (pintype "passive"))
      (node (ref "J6") (pin "@24") (pinfunction "PG_@24") (pintype "passive"))
      (node (ref "J6") (pin "P$24") (pinfunction "PG_P$24") (pintype "passive"))
      (node (ref "R21") (pin "1") (pinfunction "1_1") (pintype "passive"))
    )
    (net (code "38") (name "Net-(J18-PadSWCLK)") (class "Default")
      (node (ref "J18") (pin "SWCLK") (pinfunction "SWCLK_SWCLK") (pintype "power_in"))
      (node (ref "JTAG") (pin "4") (pinfunction "4_4") (pintype "bidirectional"))
    )
    (net (code "39") (name "Net-(J18-PadSWDIO)") (class "Default")
      (node (ref "J18") (pin "SWDIO") (pinfunction "SWDIO_SWDIO") (pintype "power_in"))
      (node (ref "JTAG") (pin "2") (pinfunction "2_2") (pintype "bidirectional"))
    )
    (net (code "40") (name "Net-(J18-PadSWO)") (class "Default")
      (node (ref "J18") (pin "SWO") (pinfunction "SWO_SWO") (pintype "power_in"))
      (node (ref "JTAG") (pin "6") (pinfunction "6_6") (pintype "bidirectional"))
    )
    (net (code "41") (name "Net-(J21-Pad2)") (class "Default")
      (node (ref "J21") (pin "2") (pinfunction "2_2") (pintype "bidirectional"))
      (node (ref "RT1") (pin "1") (pinfunction "1_1") (pintype "bidirectional"))
      (node (ref "RT2") (pin "2") (pinfunction "2_2") (pintype "bidirectional"))
      (node (ref "TP2") (pin "1") (pinfunction "1_1") (pintype "bidirectional"))
      (node (ref "TP5") (pin "1") (pinfunction "1_1") (pintype "bidirectional"))
    )
    (net (code "42") (name "Net-(JP5-Pad2)") (class "Default")
      (node (ref "JP5") (pin "2") (pinfunction "2_2") (pintype "passive"))
      (node (ref "MS1") (pin "1") (pinfunction "~{RST}_1") (pintype "input"))
      (node (ref "MS1") (pin "1'") (pinfunction "~{RST}_1'") (pintype "input"))
    )
    (net (code "43") (name "Net-(JP6-Pad2)") (class "Default")
      (node (ref "JP6") (pin "2") (pinfunction "2_2") (pintype "passive"))
      (node (ref "MS1") (pin "5") (pinfunction "A0_5") (pintype "bidirectional"))
      (node (ref "MS1") (pin "5'") (pinfunction "A0_5'") (pintype "bidirectional"))
    )
    (net (code "44") (name "Net-(JP7-Pad2)") (class "Default")
      (node (ref "JP7") (pin "2") (pinfunction "2_2") (pintype "passive"))
      (node (ref "MS1") (pin "6") (pinfunction "A1_6") (pintype "bidirectional"))
      (node (ref "MS1") (pin "6'") (pinfunction "A1_6'") (pintype "bidirectional"))
    )
    (net (code "45") (name "Net-(JP8-Pad2)") (class "Default")
      (node (ref "JP8") (pin "2") (pinfunction "2_2") (pintype "passive"))
      (node (ref "MS1") (pin "7") (pinfunction "A2_7") (pintype "bidirectional"))
      (node (ref "MS1") (pin "7'") (pinfunction "A2_7'") (pintype "bidirectional"))
    )
    (net (code "46") (name "Net-(JP9-Pad2)") (class "Default")
      (node (ref "JP9") (pin "2") (pinfunction "2_2") (pintype "passive"))
      (node (ref "MS1") (pin "8") (pinfunction "A3_8") (pintype "bidirectional"))
      (node (ref "MS1") (pin "8'") (pinfunction "A3_8'") (pintype "bidirectional"))
    )
    (net (code "47") (name "Net-(JP10-Pad2)") (class "Default")
      (node (ref "JP10") (pin "2") (pinfunction "2_2") (pintype "passive"))
      (node (ref "MS1") (pin "9") (pinfunction "A4_9") (pintype "bidirectional"))
      (node (ref "MS1") (pin "9'") (pinfunction "A4_9'") (pintype "bidirectional"))
    )
    (net (code "48") (name "Net-(JP11-Pad2)") (class "Default")
      (node (ref "JP11") (pin "2") (pinfunction "2_2") (pintype "passive"))
      (node (ref "MS1") (pin "10") (pinfunction "A5_10") (pintype "bidirectional"))
      (node (ref "MS1") (pin "10'") (pinfunction "A5_10'") (pintype "bidirectional"))
    )
    (net (code "49") (name "Net-(JP12-Pad2)") (class "Default")
      (node (ref "JP12") (pin "2") (pinfunction "2_2") (pintype "passive"))
      (node (ref "MS1") (pin "11") (pinfunction "SCK_11") (pintype "bidirectional"))
      (node (ref "MS1") (pin "11'") (pinfunction "SCK_11'") (pintype "bidirectional"))
    )
    (net (code "50") (name "Net-(JP13-Pad2)") (class "Default")
      (node (ref "JP13") (pin "2") (pinfunction "2_2") (pintype "passive"))
      (node (ref "MS1") (pin "12") (pinfunction "MOSI_12") (pintype "bidirectional"))
      (node (ref "MS1") (pin "12'") (pinfunction "MOSI_12'") (pintype "bidirectional"))
    )
    (net (code "51") (name "Net-(JP14-Pad2)") (class "Default")
      (node (ref "JP14") (pin "2") (pinfunction "2_2") (pintype "passive"))
      (node (ref "MS1") (pin "13") (pinfunction "MISO_13") (pintype "bidirectional"))
      (node (ref "MS1") (pin "13'") (pinfunction "MISO_13'") (pintype "bidirectional"))
    )
    (net (code "52") (name "Net-(JP15-Pad2)") (class "Default")
      (node (ref "JP15") (pin "2") (pinfunction "2_2") (pintype "passive"))
      (node (ref "MS1") (pin "14") (pinfunction "RX_14") (pintype "bidirectional"))
      (node (ref "MS1") (pin "14'") (pinfunction "RX_14'") (pintype "bidirectional"))
    )
    (net (code "53") (name "Net-(JP16-Pad2)") (class "Default")
      (node (ref "JP16") (pin "2") (pinfunction "2_2") (pintype "passive"))
      (node (ref "MS1") (pin "15") (pinfunction "TX_15") (pintype "bidirectional"))
      (node (ref "MS1") (pin "15'") (pinfunction "TX_15'") (pintype "bidirectional"))
    )
    (net (code "54") (name "Net-(JP17-Pad1)") (class "Default")
      (node (ref "JP17") (pin "1") (pinfunction "1_1") (pintype "passive"))
      (node (ref "MS1") (pin "28") (pinfunction "LI+_28") (pintype "power_in"))
      (node (ref "MS1") (pin "28'") (pinfunction "LI+_28'") (pintype "power_in"))
    )
    (net (code "55") (name "Net-(JP19-Pad1)") (class "Default")
      (node (ref "JP19") (pin "1") (pinfunction "1_1") (pintype "passive"))
      (node (ref "MS1") (pin "26") (pinfunction "VUSB_26") (pintype "power_in"))
      (node (ref "MS1") (pin "26'") (pinfunction "VUSB_26'") (pintype "power_in"))
    )
    (net (code "56") (name "Net-(JP20-Pad1)") (class "Default")
      (node (ref "JP20") (pin "1") (pinfunction "1_1") (pintype "passive"))
      (node (ref "MS1") (pin "25") (pinfunction "D8_25") (pintype "bidirectional"))
      (node (ref "MS1") (pin "25'") (pinfunction "D8_25'") (pintype "bidirectional"))
    )
    (net (code "57") (name "Net-(JP21-Pad1)") (class "Default")
      (node (ref "JP21") (pin "1") (pinfunction "1_1") (pintype "passive"))
      (node (ref "MS1") (pin "24") (pinfunction "D7_24") (pintype "bidirectional"))
      (node (ref "MS1") (pin "24'") (pinfunction "D7_24'") (pintype "bidirectional"))
    )
    (net (code "58") (name "Net-(JP22-Pad1)") (class "Default")
      (node (ref "JP22") (pin "1") (pinfunction "1_1") (pintype "passive"))
      (node (ref "MS1") (pin "23") (pinfunction "D6_23") (pintype "bidirectional"))
      (node (ref "MS1") (pin "23'") (pinfunction "D6_23'") (pintype "bidirectional"))
    )
    (net (code "59") (name "Net-(JP23-Pad1)") (class "Default")
      (node (ref "JP23") (pin "1") (pinfunction "1_1") (pintype "passive"))
      (node (ref "MS1") (pin "22") (pinfunction "D5_22") (pintype "bidirectional"))
      (node (ref "MS1") (pin "22'") (pinfunction "D5_22'") (pintype "bidirectional"))
    )
    (net (code "60") (name "Net-(JP24-Pad1)") (class "Default")
      (node (ref "JP24") (pin "1") (pinfunction "1_1") (pintype "passive"))
      (node (ref "MS1") (pin "21") (pinfunction "D4_21") (pintype "bidirectional"))
      (node (ref "MS1") (pin "21'") (pinfunction "D4_21'") (pintype "bidirectional"))
    )
    (net (code "61") (name "Net-(JP25-Pad1)") (class "Default")
      (node (ref "JP25") (pin "1") (pinfunction "1_1") (pintype "passive"))
      (node (ref "MS1") (pin "20") (pinfunction "D3_20") (pintype "bidirectional"))
      (node (ref "MS1") (pin "20'") (pinfunction "D3_20'") (pintype "bidirectional"))
    )
    (net (code "62") (name "Net-(JP26-Pad1)") (class "Default")
      (node (ref "JP26") (pin "1") (pinfunction "1_1") (pintype "passive"))
      (node (ref "MS1") (pin "19") (pinfunction "D2_19") (pintype "bidirectional"))
      (node (ref "MS1") (pin "19'") (pinfunction "D2_19'") (pintype "bidirectional"))
    )
    (net (code "63") (name "Net-(JP27-Pad1)") (class "Default")
      (node (ref "JP27") (pin "1") (pinfunction "1_1") (pintype "passive"))
      (node (ref "MS1") (pin "18") (pinfunction "SCL_18") (pintype "bidirectional"))
      (node (ref "MS1") (pin "18'") (pinfunction "SCL_18'") (pintype "bidirectional"))
    )
    (net (code "64") (name "Net-(JP28-Pad1)") (class "Default")
      (node (ref "JP28") (pin "1") (pinfunction "1_1") (pintype "passive"))
      (node (ref "MS1") (pin "17") (pinfunction "SDA_17") (pintype "bidirectional"))
      (node (ref "MS1") (pin "17'") (pinfunction "SDA_17'") (pintype "bidirectional"))
    )
    (net (code "65") (name "Net-(LED1-A)") (class "Default")
      (node (ref "LED1") (pin "1") (pinfunction "A_1") (pintype "bidirectional"))
      (node (ref "R16") (pin "2") (pinfunction "2_2") (pintype "passive"))
      (node (ref "R18") (pin "1") (pinfunction "1_1") (pintype "passive"))
    )
    (net (code "66") (name "Net-(LED1-K)") (class "Default")
      (node (ref "LED1") (pin "2") (pinfunction "K_2") (pintype "bidirectional"))
      (node (ref "Q1") (pin "3") (pinfunction "3_3") (pintype "bidirectional"))
      (node (ref "R22") (pin "2") (pinfunction "2_2") (pintype "passive"))
    )
    (net (code "67") (name "Net-(LED2-A)") (class "Default")
      (node (ref "JP1") (pin "2") (pinfunction "2_2") (pintype "passive"))
      (node (ref "LED2") (pin "1") (pinfunction "A_1") (pintype "bidirectional"))
    )
    (net (code "68") (name "Net-(LED2-K)") (class "Default")
      (node (ref "LED2") (pin "2") (pinfunction "K_2") (pintype "bidirectional"))
      (node (ref "R24") (pin "2") (pinfunction "2_2") (pintype "passive"))
    )
    (net (code "69") (name "Net-(LED3-K)") (class "Default")
      (node (ref "LED3") (pin "2") (pinfunction "K_2") (pintype "bidirectional"))
      (node (ref "R13") (pin "1") (pinfunction "1_1") (pintype "bidirectional"))
    )
    (net (code "70") (name "Net-(MS1-MD-Pad3')") (class "Default")
      (node (ref "MS1") (pin "3") (pinfunction "MD_3") (pintype "bidirectional"))
      (node (ref "MS1") (pin "3'") (pinfunction "MD_3'") (pintype "bidirectional"))
    )
    (net (code "71") (name "Net-(Q1-Pad1)") (class "Default")
      (node (ref "Q1") (pin "1") (pinfunction "1_1") (pintype "bidirectional"))
      (node (ref "R11") (pin "1") (pinfunction "1_1") (pintype "passive"))
      (node (ref "R17") (pin "2") (pinfunction "2_2") (pintype "passive"))
    )
    (net (code "72") (name "Net-(Q2-Pad1)") (class "Default")
      (node (ref "Q2") (pin "1") (pinfunction "1_1") (pintype "bidirectional"))
      (node (ref "Q4") (pin "1") (pinfunction "1_1") (pintype "bidirectional"))
      (node (ref "R14") (pin "2") (pinfunction "2_2") (pintype "passive"))
      (node (ref "R15") (pin "2") (pinfunction "2_2") (pintype "passive"))
    )
    (net (code "73") (name "Net-(Q2-Pad2)") (class "Default")
      (node (ref "Q2") (pin "2") (pinfunction "2_2") (pintype "bidirectional"))
      (node (ref "Q4") (pin "2") (pinfunction "2_2") (pintype "bidirectional"))
      (node (ref "R14") (pin "1") (pinfunction "1_1") (pintype "passive"))
      (node (ref "R32") (pin "1") (pinfunction "1_1") (pintype "passive"))
    )
    (net (code "74") (name "Net-(Q3-Pad1)") (class "Default")
      (node (ref "Q3") (pin "1") (pinfunction "1_1") (pintype "bidirectional"))
      (node (ref "Q5") (pin "1") (pinfunction "1_1") (pintype "bidirectional"))
      (node (ref "R30") (pin "1") (pinfunction "1_1") (pintype "passive"))
      (node (ref "R31") (pin "1") (pinfunction "1_1") (pintype "bidirectional"))
    )
    (net (code "75") (name "Net-(Q3-Pad2)") (class "Default")
      (node (ref "Q3") (pin "2") (pinfunction "2_2") (pintype "bidirectional"))
      (node (ref "Q5") (pin "2") (pinfunction "2_2") (pintype "bidirectional"))
      (node (ref "R30") (pin "2") (pinfunction "2_2") (pintype "passive"))
      (node (ref "R33") (pin "2") (pinfunction "2_2") (pintype "bidirectional"))
    )
    (net (code "76") (name "Net-(R15-Pad1)") (class "Default")
      (node (ref "R15") (pin "1") (pinfunction "1_1") (pintype "passive"))
      (node (ref "S1") (pin "2") (pinfunction "2_2") (pintype "bidirectional"))
      (node (ref "S1") (pin "5") (pinfunction "5_5") (pintype "bidirectional"))
    )
    (net (code "77") (name "Net-(R31-Pad2)") (class "Default")
      (node (ref "R31") (pin "2") (pinfunction "2_2") (pintype "bidirectional"))
      (node (ref "S4") (pin "2") (pinfunction "2_2") (pintype "bidirectional"))
      (node (ref "S4") (pin "5") (pinfunction "5_5") (pintype "bidirectional"))
    )
    (net (code "78") (name "Net-(R32-Pad2)") (class "Default")
      (node (ref "R32") (pin "2") (pinfunction "2_2") (pintype "passive"))
      (node (ref "S1") (pin "1") (pinfunction "1_1") (pintype "bidirectional"))
      (node (ref "S1") (pin "4") (pinfunction "4_4") (pintype "bidirectional"))
    )
    (net (code "79") (name "Net-(R33-Pad1)") (class "Default")
      (node (ref "R33") (pin "1") (pinfunction "1_1") (pintype "bidirectional"))
      (node (ref "S4") (pin "1") (pinfunction "1_1") (pintype "bidirectional"))
      (node (ref "S4") (pin "4") (pinfunction "4_4") (pintype "bidirectional"))
    )
    (net (code "80") (name "Net-(RGB-2)") (class "Default")
      (node (ref "R8") (pin "2") (pinfunction "2_2") (pintype "passive"))
      (node (ref "RGB") (pin "BLUE") (pinfunction "2_BLUE") (pintype "passive"))
    )
    (net (code "81") (name "Net-(RGB-3)") (class "Default")
      (node (ref "R19") (pin "2") (pinfunction "2_2") (pintype "passive"))
      (node (ref "RGB") (pin "GREEN") (pinfunction "3_GREEN") (pintype "passive"))
    )
    (net (code "82") (name "Net-(RGB-4)") (class "Default")
      (node (ref "R20") (pin "2") (pinfunction "2_2") (pintype "passive"))
      (node (ref "RGB") (pin "RED") (pinfunction "4_RED") (pintype "passive"))
    )
    (net (code "83") (name "Net-(U1-CE)") (class "Default")
      (node (ref "R2") (pin "1") (pinfunction "1_1") (pintype "passive"))
      (node (ref "R7") (pin "1") (pinfunction "1_1") (pintype "passive"))
      (node (ref "U1") (pin "4") (pinfunction "CE_4") (pintype "bidirectional"))
    )
    (net (code "84") (name "Net-(USB1-CC1)") (class "Default")
      (node (ref "R6") (pin "1") (pinfunction "1_1") (pintype "passive"))
      (node (ref "USB1") (pin "A5") (pinfunction "CC1_A5") (pintype "bidirectional"))
    )
    (net (code "85") (name "Net-(USB1-CC2)") (class "Default")
      (node (ref "R9") (pin "1") (pinfunction "1_1") (pintype "passive"))
      (node (ref "USB1") (pin "B5") (pinfunction "CC2_B5") (pintype "bidirectional"))
    )
    (net (code "86") (name "Net-(USB2-CC1)") (class "Default")
      (node (ref "R1") (pin "1") (pinfunction "1_1") (pintype "passive"))
      (node (ref "USB2") (pin "A5") (pinfunction "CC1_A5") (pintype "bidirectional"))
    )
    (net (code "87") (name "Net-(USB2-CC2)") (class "Default")
      (node (ref "R3") (pin "1") (pinfunction "1_1") (pintype "passive"))
      (node (ref "USB2") (pin "B5") (pinfunction "CC2_B5") (pintype "bidirectional"))
    )
    (net (code "88") (name "PWM0") (class "Default")
      (node (ref "J18") (pin "66") (pinfunction "D4_66") (pintype "bidirectional"))
      (node (ref "J3") (pin "52") (pinfunction "52_52") (pintype "passive"))
      (node (ref "JP24") (pin "2") (pinfunction "2_2") (pintype "passive"))
    )
    (net (code "89") (name "PWM1") (class "Default")
      (node (ref "J18") (pin "68") (pinfunction "D5_68") (pintype "bidirectional"))
      (node (ref "J3") (pin "54") (pinfunction "54_54") (pintype "passive"))
      (node (ref "JP20") (pin "2") (pinfunction "2_2") (pintype "passive"))
    )
    (net (code "90") (name "PWM2") (class "Default")
      (node (ref "J18") (pin "70") (pinfunction "D6_70") (pintype "bidirectional"))
      (node (ref "J3") (pin "56") (pinfunction "56_56") (pintype "passive"))
      (node (ref "JP22") (pin "2") (pinfunction "2_2") (pintype "passive"))
    )
    (net (code "91") (name "PWM3") (class "Default")
      (node (ref "J18") (pin "72") (pinfunction "D7_72") (pintype "bidirectional"))
      (node (ref "J3") (pin "58") (pinfunction "58_58") (pintype "passive"))
      (node (ref "JP21") (pin "2") (pinfunction "2_2") (pintype "passive"))
    )
    (net (code "92") (name "REGN") (class "Default")
      (node (ref "J6") (pin "8") (pinfunction "NC_8") (pintype "passive"))
      (node (ref "J6") (pin "@8") (pinfunction "NC_@8") (pintype "passive"))
      (node (ref "J6") (pin "P$8") (pinfunction "NC_P$8") (pintype "passive"))
      (node (ref "RT1") (pin "2") (pinfunction "2_2") (pintype "bidirectional"))
      (node (ref "TP1") (pin "1") (pinfunction "1_1") (pintype "bidirectional"))
    )
    (net (code "93") (name "RTS") (class "Default")
      (node (ref "J18") (pin "42") (pinfunction "RTS_42") (pintype "bidirectional"))
      (node (ref "J3") (pin "28") (pinfunction "28_28") (pintype "passive"))
    )
    (net (code "94") (name "RX") (class "Default")
      (node (ref "J18") (pin "38") (pinfunction "RXD_38") (pintype "bidirectional"))
      (node (ref "J3") (pin "24") (pinfunction "24_24") (pintype "passive"))
      (node (ref "JP15") (pin "1") (pinfunction "1_1") (pintype "passive"))
    )
    (net (code "95") (name "SCK") (class "Default")
      (node (ref "J18") (pin "54") (pinfunction "SCLK_54") (pintype "bidirectional"))
      (node (ref "J3") (pin "40") (pinfunction "40_40") (pintype "passive"))
      (node (ref "JP12") (pin "1") (pinfunction "1_1") (pintype "passive"))
    )
    (net (code "96") (name "SCL") (class "Default")
      (node (ref "J18") (pin "20") (pinfunction "SCL_20") (pintype "bidirectional"))
      (node (ref "J3") (pin "14") (pinfunction "14_14") (pintype "passive"))
      (node (ref "J4") (pin "4") (pinfunction "4_4") (pintype "passive"))
      (node (ref "J6") (pin "14") (pinfunction "SCL_14") (pintype "passive"))
      (node (ref "J6") (pin "@14") (pinfunction "SCL_@14") (pintype "passive"))
      (node (ref "J6") (pin "P$14") (pinfunction "SCL_P$14") (pintype "passive"))
      (node (ref "JP27") (pin "2") (pinfunction "2_2") (pintype "passive"))
    )
    (net (code "97") (name "SDA") (class "Default")
      (node (ref "J18") (pin "22") (pinfunction "SDA_22") (pintype "bidirectional"))
      (node (ref "J3") (pin "16") (pinfunction "16_16") (pintype "passive"))
      (node (ref "J4") (pin "3") (pinfunction "3_3") (pintype "passive"))
      (node (ref "J6") (pin "15") (pinfunction "SDA_15") (pintype "passive"))
      (node (ref "J6") (pin "@15") (pinfunction "SDA_@15") (pintype "passive"))
      (node (ref "J6") (pin "P$15") (pinfunction "SDA_P$15") (pintype "passive"))
      (node (ref "JP28") (pin "2") (pinfunction "2_2") (pintype "passive"))
    )
    (net (code "98") (name "SOM5") (class "Default")
      (node (ref "J18") (pin "67") (pinfunction "SIM_VCC_67") (pintype "power_in"))
      (node (ref "J3") (pin "51") (pinfunction "51_51") (pintype "passive"))
    )
    (net (code "99") (name "SOM6") (class "Default")
      (node (ref "J18") (pin "69") (pinfunction "SIM_RST_69") (pintype "bidirectional"))
      (node (ref "J3") (pin "53") (pinfunction "53_53") (pintype "passive"))
    )
    (net (code "100") (name "SOM7") (class "Default")
      (node (ref "J18") (pin "71") (pinfunction "SIM_CLK_71") (pintype "bidirectional"))
      (node (ref "J3") (pin "55") (pinfunction "55_55") (pintype "passive"))
    )
    (net (code "101") (name "SOM8") (class "Default")
      (node (ref "J18") (pin "73") (pinfunction "SIM_DATA_73") (pintype "bidirectional"))
      (node (ref "J3") (pin "57") (pinfunction "57_57") (pintype "passive"))
    )
    (net (code "102") (name "SOM9") (class "Default")
      (node (ref "J18") (pin "75") (pinfunction "NC_75") (pintype "bidirectional"))
      (node (ref "J3") (pin "60") (pinfunction "60_60") (pintype "passive"))
    )
    (net (code "103") (name "SOM10") (class "Default")
      (node (ref "J18") (pin "14") (pinfunction "NC_14") (pintype "bidirectional"))
      (node (ref "J3") (pin "10") (pinfunction "10_10") (pintype "passive"))
    )
    (net (code "104") (name "SOM11") (class "Default")
      (node (ref "J18") (pin "18") (pinfunction "GNSS_TXD_18") (pintype "bidirectional"))
      (node (ref "J3") (pin "12") (pinfunction "12_12") (pintype "passive"))
    )
    (net (code "105") (name "SOM12") (class "Default")
      (node (ref "J18") (pin "58") (pinfunction "D24_58") (pintype "bidirectional"))
      (node (ref "J3") (pin "44") (pinfunction "44_44") (pintype "passive"))
    )
    (net (code "106") (name "SOM13") (class "Default")
      (node (ref "J18") (pin "60") (pinfunction "D25_60") (pintype "bidirectional"))
      (node (ref "J3") (pin "46") (pinfunction "46_46") (pintype "passive"))
    )
    (net (code "107") (name "SOM14") (class "Default")
      (node (ref "J18") (pin "51") (pinfunction "NC_51") (pintype "bidirectional"))
      (node (ref "J3") (pin "35") (pinfunction "35_35") (pintype "passive"))
    )
    (net (code "108") (name "SOM15") (class "Default")
      (node (ref "J18") (pin "53") (pinfunction "SWD_CLK_53") (pintype "bidirectional"))
      (node (ref "J3") (pin "37") (pinfunction "37_37") (pintype "passive"))
    )
    (net (code "109") (name "SOM16") (class "Default")
      (node (ref "J18") (pin "55") (pinfunction "SWD_DATA_55") (pintype "bidirectional"))
      (node (ref "J3") (pin "39") (pinfunction "39_39") (pintype "passive"))
    )
    (net (code "110") (name "SOM17") (class "Default")
      (node (ref "J18") (pin "57") (pinfunction "D27_57") (pintype "bidirectional"))
      (node (ref "J3") (pin "41") (pinfunction "41_41") (pintype "bidirectional"))
    )
    (net (code "111") (name "SOM18") (class "Default")
      (node (ref "J18") (pin "59") (pinfunction "D26_59") (pintype "bidirectional"))
      (node (ref "J3") (pin "43") (pinfunction "43_43") (pintype "passive"))
    )
    (net (code "112") (name "TS") (class "Default")
      (node (ref "J21") (pin "1") (pinfunction "1_1") (pintype "bidirectional"))
      (node (ref "J6") (pin "17") (pinfunction "TS_17") (pintype "passive"))
      (node (ref "J6") (pin "@17") (pinfunction "TS_@17") (pintype "passive"))
      (node (ref "J6") (pin "P$17") (pinfunction "TS_P$17") (pintype "passive"))
      (node (ref "R23") (pin "1") (pinfunction "1_1") (pintype "passive"))
    )
    (net (code "113") (name "TX") (class "Default")
      (node (ref "J18") (pin "36") (pinfunction "TXD_36") (pintype "bidirectional"))
      (node (ref "J3") (pin "22") (pinfunction "22_22") (pintype "passive"))
      (node (ref "JP16") (pin "1") (pinfunction "1_1") (pintype "passive"))
    )
    (net (code "114") (name "UB_USB_N") (class "Default")
      (node (ref "D23") (pin "1") (pinfunction "1_1") (pintype "bidirectional"))
      (node (ref "J18") (pin "46") (pinfunction "UB_USB_N_46") (pintype "bidirectional"))
      (node (ref "USB2") (pin "A7") (pinfunction "D-_A7") (pintype "bidirectional"))
      (node (ref "USB2") (pin "B7") (pinfunction "D-_B7") (pintype "bidirectional"))
    )
    (net (code "115") (name "UB_USB_P") (class "Default")
      (node (ref "D23") (pin "4") (pinfunction "4_4") (pintype "bidirectional"))
      (node (ref "J18") (pin "44") (pinfunction "UB_USB_P_44") (pintype "bidirectional"))
      (node (ref "USB2") (pin "A6") (pinfunction "D+_A6") (pintype "bidirectional"))
      (node (ref "USB2") (pin "B6") (pinfunction "D+_B6") (pintype "bidirectional"))
    )
    (net (code "116") (name "UB_VBUS") (class "Default")
      (node (ref "D23") (pin "5") (pinfunction "5_5") (pintype "bidirectional"))
      (node (ref "F4") (pin "P$2") (pinfunction "2_P$2") (pintype "bidirectional"))
      (node (ref "USB2") (pin "VBUS1") (pinfunction "VBUS_VBUS1") (pintype "bidirectional"))
      (node (ref "USB2") (pin "VBUS2") (pinfunction "VBUS_VBUS2") (pintype "bidirectional"))
    )
    (net (code "117") (name "UB_VBUS1") (class "Default")
      (node (ref "F4") (pin "P$1") (pinfunction "1_P$1") (pintype "bidirectional"))
      (node (ref "J18") (pin "74") (pinfunction "MODEM_VBUS_74") (pintype "power_in"))
    )
    (net (code "118") (name "USB_N") (class "Default")
      (node (ref "D1") (pin "1") (pinfunction "1_1") (pintype "bidirectional"))
      (node (ref "J18") (pin "13") (pinfunction "USB_N_13") (pintype "bidirectional"))
      (node (ref "USB1") (pin "A7") (pinfunction "D-_A7") (pintype "bidirectional"))
      (node (ref "USB1") (pin "B7") (pinfunction "D-_B7") (pintype "bidirectional"))
    )
    (net (code "119") (name "USB_P") (class "Default")
      (node (ref "D1") (pin "4") (pinfunction "4_4") (pintype "bidirectional"))
      (node (ref "J18") (pin "11") (pinfunction "USB_P_11") (pintype "bidirectional"))
      (node (ref "USB1") (pin "A6") (pinfunction "D+_A6") (pintype "bidirectional"))
      (node (ref "USB1") (pin "B6") (pinfunction "D+_B6") (pintype "bidirectional"))
    )
    (net (code "120") (name "VBAT") (class "Default")
      (node (ref "J6") (pin "18") (pinfunction "VBAT_18") (pintype "passive"))
      (node (ref "J6") (pin "19") (pinfunction "VBAT_19") (pintype "passive"))
      (node (ref "J6") (pin "20") (pinfunction "VBAT_20") (pintype "passive"))
      (node (ref "J6") (pin "@18") (pinfunction "VBAT_@18") (pintype "passive"))
      (node (ref "J6") (pin "@19") (pinfunction "VBAT_@19") (pintype "passive"))
      (node (ref "J6") (pin "@20") (pinfunction "VBAT_@20") (pintype "passive"))
      (node (ref "J6") (pin "P$18") (pinfunction "VBAT_P$18") (pintype "passive"))
      (node (ref "J6") (pin "P$19") (pinfunction "VBAT_P$19") (pintype "passive"))
      (node (ref "J6") (pin "P$20") (pinfunction "VBAT_P$20") (pintype "passive"))
      (node (ref "JP17") (pin "2") (pinfunction "2_2") (pintype "passive"))
      (node (ref "Q3") (pin "3") (pinfunction "3_3") (pintype "bidirectional"))
      (node (ref "VBAT") (pin "1") (pinfunction "TP_1") (pintype "bidirectional"))
    )
    (net (code "121") (name "VBUS") (class "Default")
      (node (ref "F2") (pin "P$2") (pinfunction "2_P$2") (pintype "bidirectional"))
      (node (ref "U1") (pin "5") (pinfunction "VIN_5") (pintype "power_in"))
    )
    (net (code "122") (name "VCC") (class "Default")
      (node (ref "C10") (pin "1") (pinfunction "1_1") (pintype "passive"))
      (node (ref "C20") (pin "1") (pinfunction "1_1") (pintype "passive"))
      (node (ref "C61") (pin "1") (pinfunction "1_1") (pintype "passive"))
      (node (ref "C8") (pin "1") (pinfunction "1_1") (pintype "passive"))
      (node (ref "C9") (pin "1") (pinfunction "1_1") (pintype "passive"))
      (node (ref "D16") (pin "2") (pinfunction "P$2_2") (pintype "bidirectional"))
      (node (ref "J18") (pin "2") (pinfunction "VCC_2") (pintype "power_in"))
      (node (ref "J18") (pin "4") (pinfunction "VCC_4") (pintype "power_in"))
      (node (ref "J18") (pin "6") (pinfunction "VCC_6") (pintype "power_in"))
      (node (ref "J18") (pin "8") (pinfunction "VCC_8") (pintype "power_in"))
      (node (ref "J3") (pin "2") (pinfunction "2_2") (pintype "passive"))
      (node (ref "J3") (pin "4") (pinfunction "4_4") (pintype "passive"))
      (node (ref "J3") (pin "6") (pinfunction "6_6") (pintype "passive"))
      (node (ref "J6") (pin "5") (pinfunction "VCC_5") (pintype "passive"))
      (node (ref "J6") (pin "6") (pinfunction "VCC_6") (pintype "passive"))
      (node (ref "J6") (pin "@5") (pinfunction "VCC_@5") (pintype "passive"))
      (node (ref "J6") (pin "@6") (pinfunction "VCC_@6") (pintype "passive"))
      (node (ref "J6") (pin "P$5") (pinfunction "VCC_P$5") (pintype "passive"))
      (node (ref "J6") (pin "P$6") (pinfunction "VCC_P$6") (pintype "passive"))
      (node (ref "VCC") (pin "1") (pinfunction "TP_1") (pintype "bidirectional"))
    )
    (net (code "123") (name "VIN") (class "Default")
      (node (ref "J6") (pin "11") (pinfunction "VIN_11") (pintype "passive"))
      (node (ref "J6") (pin "12") (pinfunction "VIN_12") (pintype "passive"))
      (node (ref "J6") (pin "@11") (pinfunction "VIN_@11") (pintype "passive"))
      (node (ref "J6") (pin "@12") (pinfunction "VIN_@12") (pintype "passive"))
      (node (ref "J6") (pin "P$11") (pinfunction "VIN_P$11") (pintype "passive"))
      (node (ref "J6") (pin "P$12") (pinfunction "VIN_P$12") (pintype "passive"))
      (node (ref "Q4") (pin "3") (pinfunction "3_3") (pintype "bidirectional"))
      (node (ref "R11") (pin "2") (pinfunction "2_2") (pintype "passive"))
      (node (ref "R18") (pin "2") (pinfunction "2_2") (pintype "passive"))
      (node (ref "VIN") (pin "1") (pinfunction "TP_1") (pintype "bidirectional"))
    )
    (net (code "124") (name "VUSB") (class "Default")
      (node (ref "D1") (pin "5") (pinfunction "5_5") (pintype "bidirectional"))
      (node (ref "F2") (pin "P$1") (pinfunction "1_P$1") (pintype "bidirectional"))
      (node (ref "USB1") (pin "VBUS1") (pinfunction "VBUS_VBUS1") (pintype "bidirectional"))
      (node (ref "USB1") (pin "VBUS2") (pinfunction "VBUS_VBUS2") (pintype "bidirectional"))
    )
    (net (code "125") (name "VUSB-MCU") (class "Default")
      (node (ref "J18") (pin "16") (pinfunction "NC_16") (pintype "power_in"))
      (node (ref "JP19") (pin "2") (pinfunction "2_2") (pintype "passive"))
      (node (ref "U1") (pin "1") (pinfunction "VOUT_1") (pintype "power_in"))
    )
    (net (code "126") (name "unconnected-(D1-Pad3)") (class "Default")
      (node (ref "D1") (pin "3") (pinfunction "3_3") (pintype "bidirectional"))
    )
    (net (code "127") (name "unconnected-(D1-Pad6)") (class "Default")
      (node (ref "D1") (pin "6") (pinfunction "6_6") (pintype "bidirectional"))
    )
    (net (code "128") (name "unconnected-(D23-Pad3)") (class "Default")
      (node (ref "D23") (pin "3") (pinfunction "3_3") (pintype "bidirectional"))
    )
    (net (code "129") (name "unconnected-(D23-Pad6)") (class "Default")
      (node (ref "D23") (pin "6") (pinfunction "6_6") (pintype "bidirectional"))
    )
    (net (code "130") (name "unconnected-(J3-Pad30)") (class "Default")
      (node (ref "J3") (pin "30") (pinfunction "30_30") (pintype "passive"))
    )
    (net (code "131") (name "unconnected-(J3-Pad32)") (class "Default")
      (node (ref "J3") (pin "32") (pinfunction "32_32") (pintype "passive"))
    )
    (net (code "132") (name "unconnected-(J11-5-PadNC1)") (class "Default")
      (node (ref "J11") (pin "NC1") (pinfunction "5_NC1") (pintype "bidirectional"))
    )
    (net (code "133") (name "unconnected-(J11-6-PadNC2)") (class "Default")
      (node (ref "J11") (pin "NC2") (pinfunction "6_NC2") (pintype "bidirectional"))
    )
    (net (code "134") (name "unconnected-(JTAG-Pad7)") (class "Default")
      (node (ref "JTAG") (pin "7") (pinfunction "7_7") (pintype "bidirectional"))
    )
    (net (code "135") (name "unconnected-(JTAG-Pad8)") (class "Default")
      (node (ref "JTAG") (pin "8") (pinfunction "8_8") (pintype "bidirectional"))
    )
    (net (code "136") (name "unconnected-(U1-FLG-Pad3)") (class "Default")
      (node (ref "U1") (pin "3") (pinfunction "FLG_3") (pintype "bidirectional"))
    )
    (net (code "137") (name "unconnected-(X1-Pad1)") (class "Default")
      (node (ref "X1") (pin "1") (pinfunction "1_1") (pintype "passive"))
    )
    (net (code "138") (name "unconnected-(X2-Pad1)") (class "Default")
      (node (ref "X2") (pin "1") (pinfunction "1_1") (pintype "passive"))
    )
    (net (code "139") (name "unconnected-(X3-Pad1)") (class "Default")
      (node (ref "X3") (pin "1") (pinfunction "1_1") (pintype "passive"))
    )
    (net (code "140") (name "~{MODE}") (class "Default")
      (node (ref "J18") (pin "32") (pinfunction "~{MODE}_32") (pintype "bidirectional"))
      (node (ref "J3") (pin "18") (pinfunction "18_18") (pintype "passive"))
      (node (ref "R12") (pin "1") (pinfunction "1_1") (pintype "passive"))
      (node (ref "S2") (pin "3") (pinfunction "3_3") (pintype "passive"))
      (node (ref "S2") (pin "4") (pinfunction "4_4") (pintype "passive"))
    )
    (net (code "141") (name "~{RESET}") (class "Default")
      (node (ref "C1") (pin "1") (pinfunction "1_1") (pintype "passive"))
      (node (ref "J18") (pin "!RESET") (pinfunction "~{RESET}_!RESET") (pintype "power_in"))
      (node (ref "J18") (pin "34") (pinfunction "~{RESET}_34") (pintype "bidirectional"))
      (node (ref "J3") (pin "20") (pinfunction "20_20") (pintype "passive"))
      (node (ref "J6") (pin "23") (pinfunction "~{RST}_23") (pintype "passive"))
      (node (ref "J6") (pin "@23") (pinfunction "~{RST}_@23") (pintype "passive"))
      (node (ref "J6") (pin "P$23") (pinfunction "~{RST}_P$23") (pintype "passive"))
      (node (ref "JP5") (pin "1") (pinfunction "1_1") (pintype "passive"))
      (node (ref "JTAG") (pin "10") (pinfunction "10_10") (pintype "bidirectional"))
      (node (ref "R4") (pin "1") (pinfunction "1_1") (pintype "passive"))
      (node (ref "S3") (pin "3") (pinfunction "3_3") (pintype "passive"))
      (node (ref "S3") (pin "4") (pinfunction "4_4") (pintype "passive"))
    )
  )
)
